# KeyBoard.net
KiCad netlist of a schematic drawn in Altium Designer
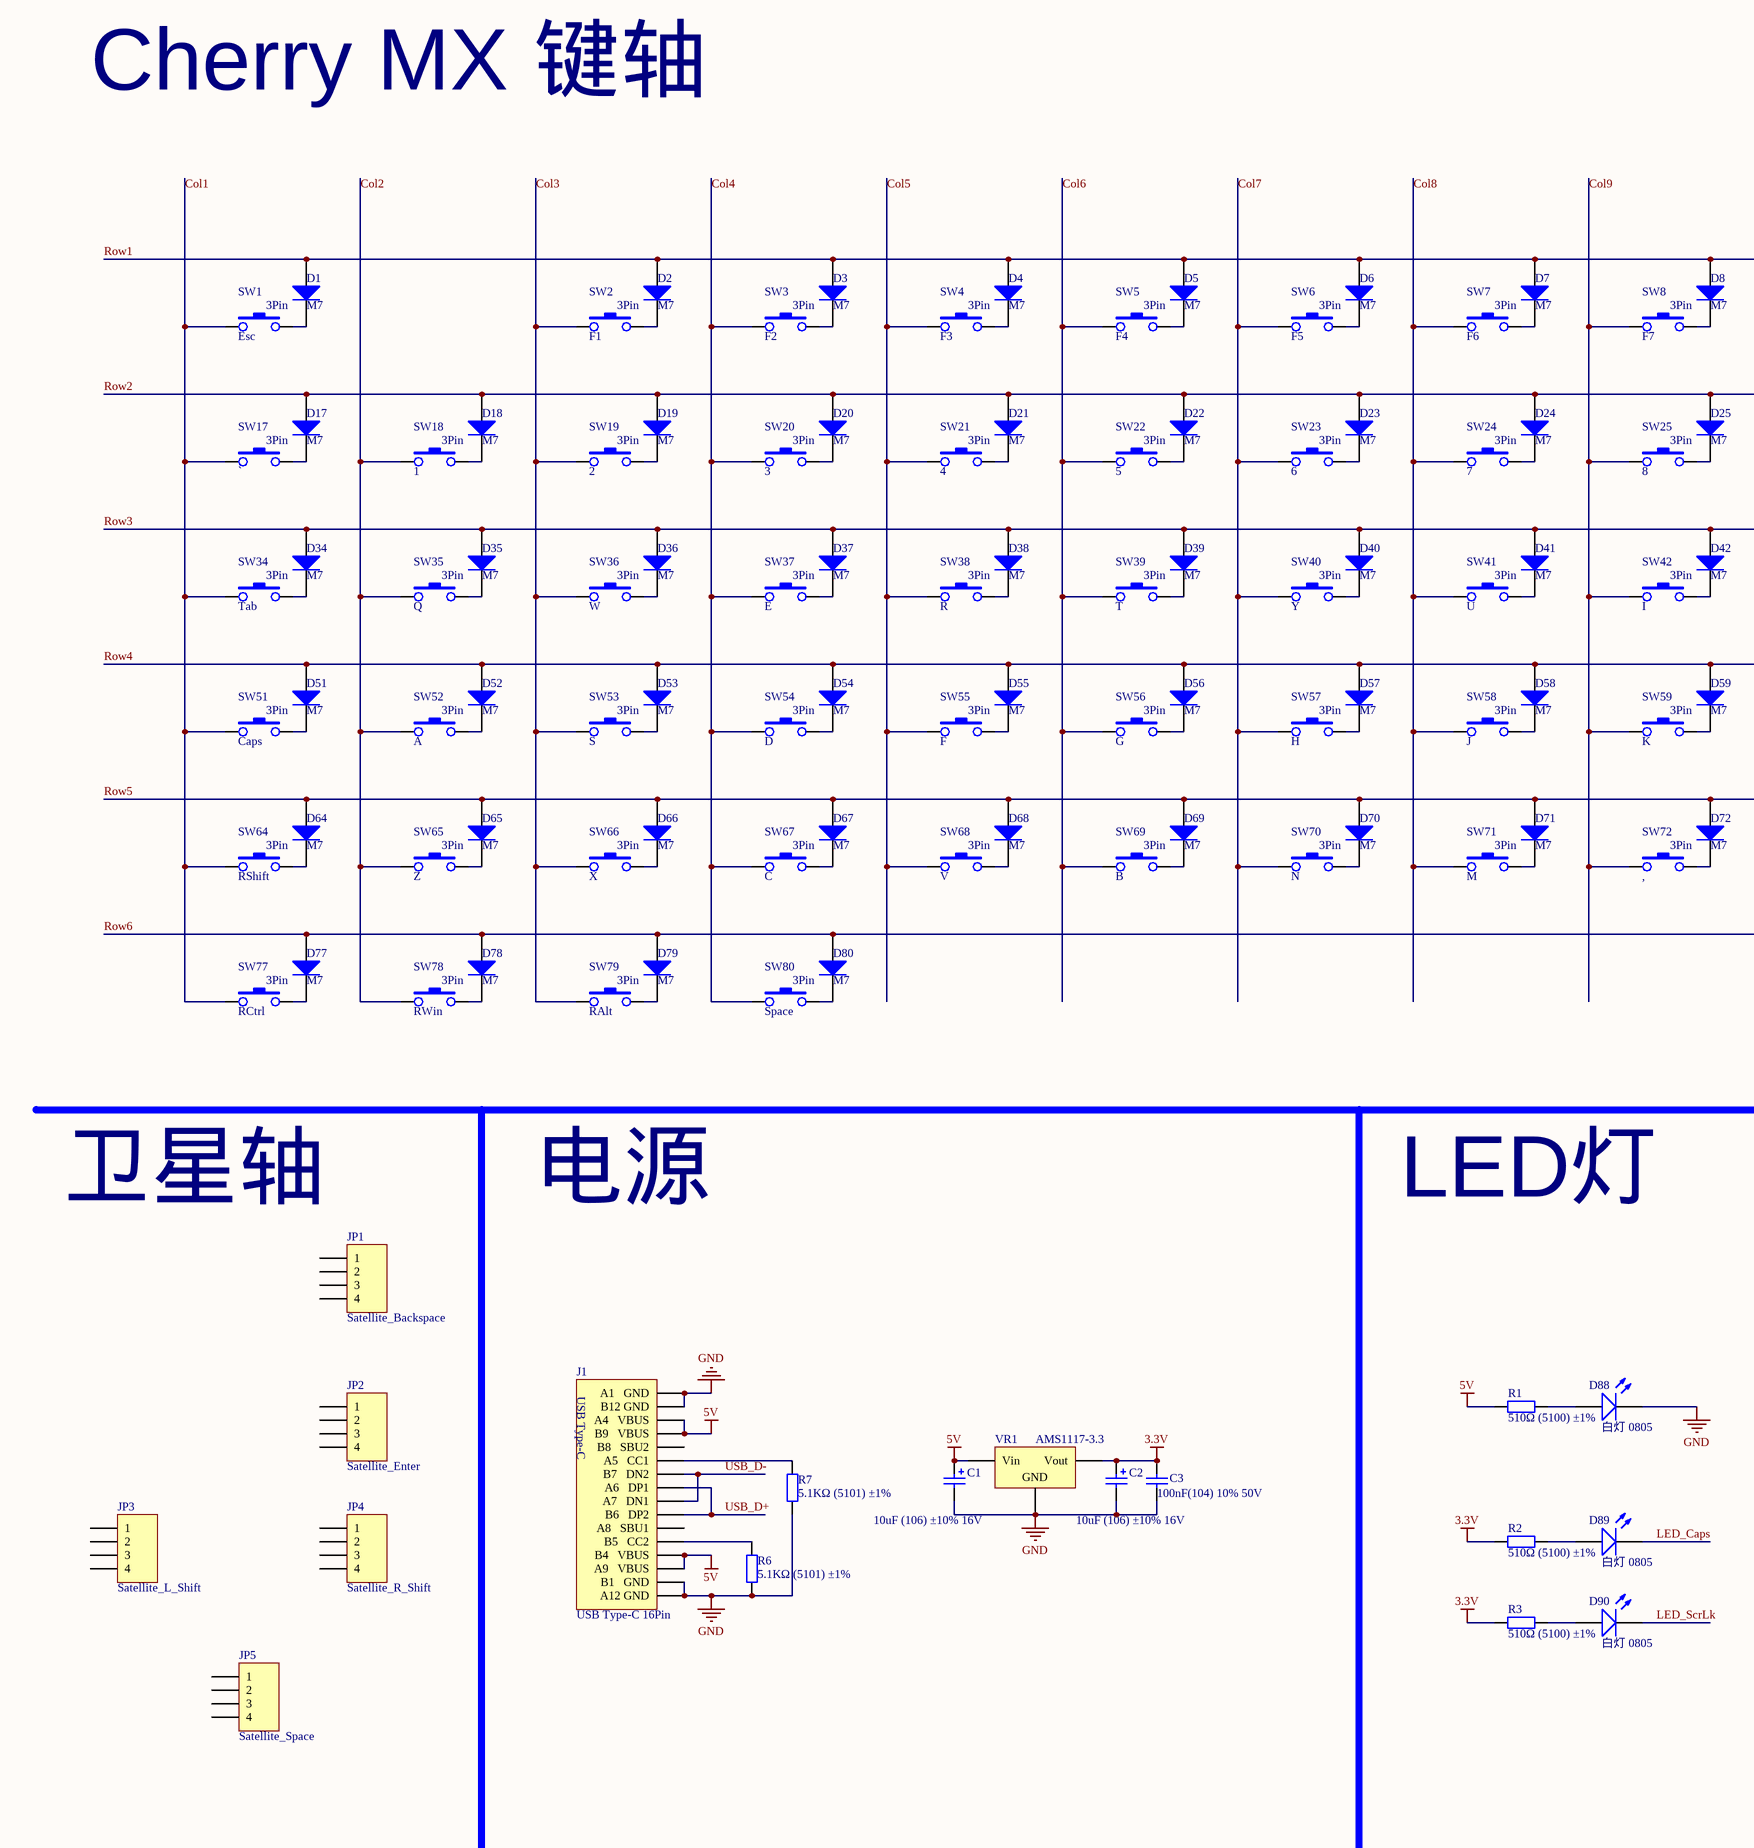
[diagram p0: KeyBoard.SchDoc, left]
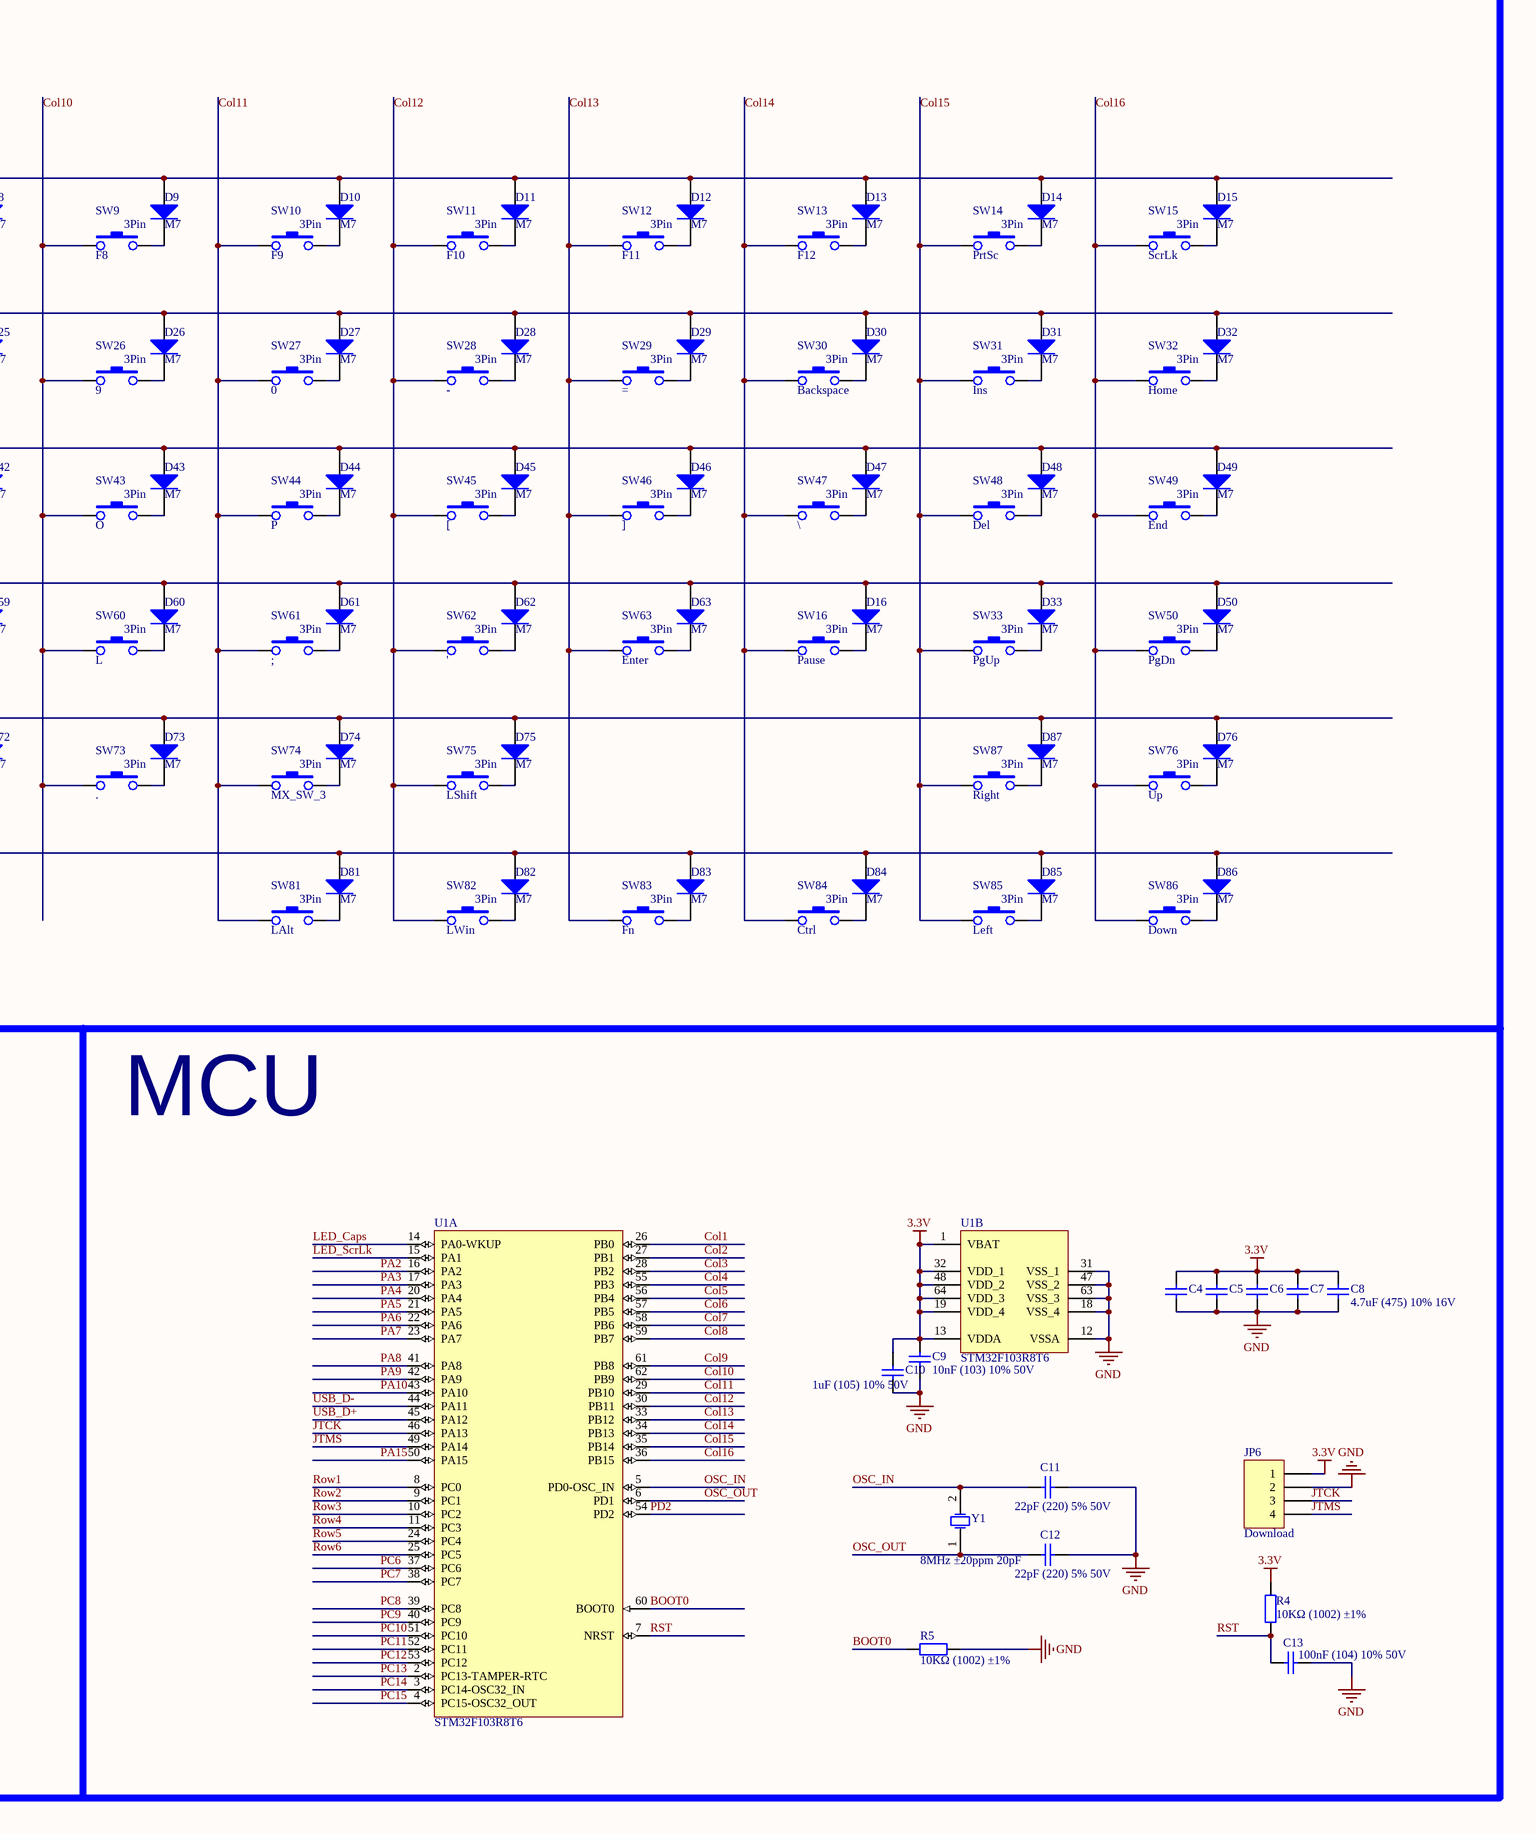
[diagram p1: KeyBoard.SchDoc, right]

(export (version "E")
  (design (tool "Eeschema 10.0.6"))
  (components
    (comp (ref "C1")
      (value "10uF (106) ±10% 16V")
      (footprint "CASE-A_3216")
      (description "钽电容")
      (libsource (lib "Miscellaneous Devices LC") (part "3216 10uF (106) 10% 16V"))
    )
    (comp (ref "C2")
      (value "10uF (106) ±10% 16V")
      (footprint "CASE-A_3216")
      (description "钽电容")
      (libsource (lib "Miscellaneous Devices LC") (part "3216 10uF (106) 10% 16V"))
    )
    (comp (ref "C3")
      (value "100nF(104) 10% 50V")
      (footprint "0805_C")
      (description "贴片电容")
      (libsource (lib "Miscellaneous Devices LC") (part "0805 100nF(104) 10% 50V"))
    )
    (comp (ref "C4")
      (value "100nF (104) 10% 50V")
      (footprint "0603_C")
      (description "贴片电容")
      (libsource (lib "Miscellaneous Devices LC") (part "0603 100nF (104) 10% 50V"))
    )
    (comp (ref "C5")
      (value "100nF (104) 10% 50V")
      (footprint "0603_C")
      (description "贴片电容")
      (libsource (lib "Miscellaneous Devices LC") (part "0603 100nF (104) 10% 50V"))
    )
    (comp (ref "C6")
      (value "100nF (104) 10% 50V")
      (footprint "0603_C")
      (description "贴片电容")
      (libsource (lib "Miscellaneous Devices LC") (part "0603 100nF (104) 10% 50V"))
    )
    (comp (ref "C7")
      (value "100nF (104) 10% 50V")
      (footprint "0603_C")
      (description "贴片电容")
      (libsource (lib "Miscellaneous Devices LC") (part "0603 100nF (104) 10% 50V"))
    )
    (comp (ref "C8")
      (value "4.7uF (475) 10% 16V")
      (footprint "0603_C")
      (description "贴片电容")
      (libsource (lib "Miscellaneous Devices LC") (part "0603 4.7uF (475) 10% 16V"))
    )
    (comp (ref "C9")
      (value "10nF (103) 10% 50V")
      (footprint "0603_C")
      (description "贴片电容")
      (libsource (lib "Miscellaneous Devices LC") (part "0603 10nF (103) 10% 50V"))
    )
    (comp (ref "C10")
      (value "1uF (105) 10% 50V")
      (footprint "0603_C")
      (description "贴片电容")
      (libsource (lib "Miscellaneous Devices LC") (part "0603 1uF (105) 10% 50V"))
    )
    (comp (ref "C11")
      (value "22pF (220) 5% 50V")
      (footprint "0603_C")
      (description "贴片电容")
      (libsource (lib "Miscellaneous Devices LC") (part "0603 22pF (220) 5% 50V"))
    )
    (comp (ref "C12")
      (value "22pF (220) 5% 50V")
      (footprint "0603_C")
      (description "贴片电容")
      (libsource (lib "Miscellaneous Devices LC") (part "0603 22pF (220) 5% 50V"))
    )
    (comp (ref "C13")
      (value "100nF (104) 10% 50V")
      (footprint "0603_C")
      (description "贴片电容")
      (libsource (lib "Miscellaneous Devices LC") (part "0603 100nF (104) 10% 50V"))
    )
    (comp (ref "D1")
      (value "M7")
      (footprint "SMA(DO-214AC)_S1")
      (description "二极管")
      (libsource (lib "Miscellaneous Devices LC") (part "SMA(DO-214AC) M7"))
    )
    (comp (ref "D2")
      (value "M7")
      (footprint "SMA(DO-214AC)_S1")
      (description "二极管")
      (libsource (lib "Miscellaneous Devices LC") (part "SMA(DO-214AC) M7"))
    )
    (comp (ref "D3")
      (value "M7")
      (footprint "SMA(DO-214AC)_S1")
      (description "二极管")
      (libsource (lib "Miscellaneous Devices LC") (part "SMA(DO-214AC) M7"))
    )
    (comp (ref "D4")
      (value "M7")
      (footprint "SMA(DO-214AC)_S1")
      (description "二极管")
      (libsource (lib "Miscellaneous Devices LC") (part "SMA(DO-214AC) M7"))
    )
    (comp (ref "D5")
      (value "M7")
      (footprint "SMA(DO-214AC)_S1")
      (description "二极管")
      (libsource (lib "Miscellaneous Devices LC") (part "SMA(DO-214AC) M7"))
    )
    (comp (ref "D6")
      (value "M7")
      (footprint "SMA(DO-214AC)_S1")
      (description "二极管")
      (libsource (lib "Miscellaneous Devices LC") (part "SMA(DO-214AC) M7"))
    )
    (comp (ref "D7")
      (value "M7")
      (footprint "SMA(DO-214AC)_S1")
      (description "二极管")
      (libsource (lib "Miscellaneous Devices LC") (part "SMA(DO-214AC) M7"))
    )
    (comp (ref "D8")
      (value "M7")
      (footprint "SMA(DO-214AC)_S1")
      (description "二极管")
      (libsource (lib "Miscellaneous Devices LC") (part "SMA(DO-214AC) M7"))
    )
    (comp (ref "D9")
      (value "M7")
      (footprint "SMA(DO-214AC)_S1")
      (description "二极管")
      (libsource (lib "Miscellaneous Devices LC") (part "SMA(DO-214AC) M7"))
    )
    (comp (ref "D10")
      (value "M7")
      (footprint "SMA(DO-214AC)_S1")
      (description "二极管")
      (libsource (lib "Miscellaneous Devices LC") (part "SMA(DO-214AC) M7"))
    )
    (comp (ref "D11")
      (value "M7")
      (footprint "SMA(DO-214AC)_S1")
      (description "二极管")
      (libsource (lib "Miscellaneous Devices LC") (part "SMA(DO-214AC) M7"))
    )
    (comp (ref "D12")
      (value "M7")
      (footprint "SMA(DO-214AC)_S1")
      (description "二极管")
      (libsource (lib "Miscellaneous Devices LC") (part "SMA(DO-214AC) M7"))
    )
    (comp (ref "D13")
      (value "M7")
      (footprint "SMA(DO-214AC)_S1")
      (description "二极管")
      (libsource (lib "Miscellaneous Devices LC") (part "SMA(DO-214AC) M7"))
    )
    (comp (ref "D14")
      (value "M7")
      (footprint "SMA(DO-214AC)_S1")
      (description "二极管")
      (libsource (lib "Miscellaneous Devices LC") (part "SMA(DO-214AC) M7"))
    )
    (comp (ref "D15")
      (value "M7")
      (footprint "SMA(DO-214AC)_S1")
      (description "二极管")
      (libsource (lib "Miscellaneous Devices LC") (part "SMA(DO-214AC) M7"))
    )
    (comp (ref "D16")
      (value "M7")
      (footprint "SMA(DO-214AC)_S1")
      (description "二极管")
      (libsource (lib "Miscellaneous Devices LC") (part "SMA(DO-214AC) M7"))
    )
    (comp (ref "D17")
      (value "M7")
      (footprint "SMA(DO-214AC)_S1")
      (description "二极管")
      (libsource (lib "Miscellaneous Devices LC") (part "SMA(DO-214AC) M7"))
    )
    (comp (ref "D18")
      (value "M7")
      (footprint "SMA(DO-214AC)_S1")
      (description "二极管")
      (libsource (lib "Miscellaneous Devices LC") (part "SMA(DO-214AC) M7"))
    )
    (comp (ref "D19")
      (value "M7")
      (footprint "SMA(DO-214AC)_S1")
      (description "二极管")
      (libsource (lib "Miscellaneous Devices LC") (part "SMA(DO-214AC) M7"))
    )
    (comp (ref "D20")
      (value "M7")
      (footprint "SMA(DO-214AC)_S1")
      (description "二极管")
      (libsource (lib "Miscellaneous Devices LC") (part "SMA(DO-214AC) M7"))
    )
    (comp (ref "D21")
      (value "M7")
      (footprint "SMA(DO-214AC)_S1")
      (description "二极管")
      (libsource (lib "Miscellaneous Devices LC") (part "SMA(DO-214AC) M7"))
    )
    (comp (ref "D22")
      (value "M7")
      (footprint "SMA(DO-214AC)_S1")
      (description "二极管")
      (libsource (lib "Miscellaneous Devices LC") (part "SMA(DO-214AC) M7"))
    )
    (comp (ref "D23")
      (value "M7")
      (footprint "SMA(DO-214AC)_S1")
      (description "二极管")
      (libsource (lib "Miscellaneous Devices LC") (part "SMA(DO-214AC) M7"))
    )
    (comp (ref "D24")
      (value "M7")
      (footprint "SMA(DO-214AC)_S1")
      (description "二极管")
      (libsource (lib "Miscellaneous Devices LC") (part "SMA(DO-214AC) M7"))
    )
    (comp (ref "D25")
      (value "M7")
      (footprint "SMA(DO-214AC)_S1")
      (description "二极管")
      (libsource (lib "Miscellaneous Devices LC") (part "SMA(DO-214AC) M7"))
    )
    (comp (ref "D26")
      (value "M7")
      (footprint "SMA(DO-214AC)_S1")
      (description "二极管")
      (libsource (lib "Miscellaneous Devices LC") (part "SMA(DO-214AC) M7"))
    )
    (comp (ref "D27")
      (value "M7")
      (footprint "SMA(DO-214AC)_S1")
      (description "二极管")
      (libsource (lib "Miscellaneous Devices LC") (part "SMA(DO-214AC) M7"))
    )
    (comp (ref "D28")
      (value "M7")
      (footprint "SMA(DO-214AC)_S1")
      (description "二极管")
      (libsource (lib "Miscellaneous Devices LC") (part "SMA(DO-214AC) M7"))
    )
    (comp (ref "D29")
      (value "M7")
      (footprint "SMA(DO-214AC)_S1")
      (description "二极管")
      (libsource (lib "Miscellaneous Devices LC") (part "SMA(DO-214AC) M7"))
    )
    (comp (ref "D30")
      (value "M7")
      (footprint "SMA(DO-214AC)_S1")
      (description "二极管")
      (libsource (lib "Miscellaneous Devices LC") (part "SMA(DO-214AC) M7"))
    )
    (comp (ref "D31")
      (value "M7")
      (footprint "SMA(DO-214AC)_S1")
      (description "二极管")
      (libsource (lib "Miscellaneous Devices LC") (part "SMA(DO-214AC) M7"))
    )
    (comp (ref "D32")
      (value "M7")
      (footprint "SMA(DO-214AC)_S1")
      (description "二极管")
      (libsource (lib "Miscellaneous Devices LC") (part "SMA(DO-214AC) M7"))
    )
    (comp (ref "D33")
      (value "M7")
      (footprint "SMA(DO-214AC)_S1")
      (description "二极管")
      (libsource (lib "Miscellaneous Devices LC") (part "SMA(DO-214AC) M7"))
    )
    (comp (ref "D34")
      (value "M7")
      (footprint "SMA(DO-214AC)_S1")
      (description "二极管")
      (libsource (lib "Miscellaneous Devices LC") (part "SMA(DO-214AC) M7"))
    )
    (comp (ref "D35")
      (value "M7")
      (footprint "SMA(DO-214AC)_S1")
      (description "二极管")
      (libsource (lib "Miscellaneous Devices LC") (part "SMA(DO-214AC) M7"))
    )
    (comp (ref "D36")
      (value "M7")
      (footprint "SMA(DO-214AC)_S1")
      (description "二极管")
      (libsource (lib "Miscellaneous Devices LC") (part "SMA(DO-214AC) M7"))
    )
    (comp (ref "D37")
      (value "M7")
      (footprint "SMA(DO-214AC)_S1")
      (description "二极管")
      (libsource (lib "Miscellaneous Devices LC") (part "SMA(DO-214AC) M7"))
    )
    (comp (ref "D38")
      (value "M7")
      (footprint "SMA(DO-214AC)_S1")
      (description "二极管")
      (libsource (lib "Miscellaneous Devices LC") (part "SMA(DO-214AC) M7"))
    )
    (comp (ref "D39")
      (value "M7")
      (footprint "SMA(DO-214AC)_S1")
      (description "二极管")
      (libsource (lib "Miscellaneous Devices LC") (part "SMA(DO-214AC) M7"))
    )
    (comp (ref "D40")
      (value "M7")
      (footprint "SMA(DO-214AC)_S1")
      (description "二极管")
      (libsource (lib "Miscellaneous Devices LC") (part "SMA(DO-214AC) M7"))
    )
    (comp (ref "D41")
      (value "M7")
      (footprint "SMA(DO-214AC)_S1")
      (description "二极管")
      (libsource (lib "Miscellaneous Devices LC") (part "SMA(DO-214AC) M7"))
    )
    (comp (ref "D42")
      (value "M7")
      (footprint "SMA(DO-214AC)_S1")
      (description "二极管")
      (libsource (lib "Miscellaneous Devices LC") (part "SMA(DO-214AC) M7"))
    )
    (comp (ref "D43")
      (value "M7")
      (footprint "SMA(DO-214AC)_S1")
      (description "二极管")
      (libsource (lib "Miscellaneous Devices LC") (part "SMA(DO-214AC) M7"))
    )
    (comp (ref "D44")
      (value "M7")
      (footprint "SMA(DO-214AC)_S1")
      (description "二极管")
      (libsource (lib "Miscellaneous Devices LC") (part "SMA(DO-214AC) M7"))
    )
    (comp (ref "D45")
      (value "M7")
      (footprint "SMA(DO-214AC)_S1")
      (description "二极管")
      (libsource (lib "Miscellaneous Devices LC") (part "SMA(DO-214AC) M7"))
    )
    (comp (ref "D46")
      (value "M7")
      (footprint "SMA(DO-214AC)_S1")
      (description "二极管")
      (libsource (lib "Miscellaneous Devices LC") (part "SMA(DO-214AC) M7"))
    )
    (comp (ref "D47")
      (value "M7")
      (footprint "SMA(DO-214AC)_S1")
      (description "二极管")
      (libsource (lib "Miscellaneous Devices LC") (part "SMA(DO-214AC) M7"))
    )
    (comp (ref "D48")
      (value "M7")
      (footprint "SMA(DO-214AC)_S1")
      (description "二极管")
      (libsource (lib "Miscellaneous Devices LC") (part "SMA(DO-214AC) M7"))
    )
    (comp (ref "D49")
      (value "M7")
      (footprint "SMA(DO-214AC)_S1")
      (description "二极管")
      (libsource (lib "Miscellaneous Devices LC") (part "SMA(DO-214AC) M7"))
    )
    (comp (ref "D50")
      (value "M7")
      (footprint "SMA(DO-214AC)_S1")
      (description "二极管")
      (libsource (lib "Miscellaneous Devices LC") (part "SMA(DO-214AC) M7"))
    )
    (comp (ref "D51")
      (value "M7")
      (footprint "SMA(DO-214AC)_S1")
      (description "二极管")
      (libsource (lib "Miscellaneous Devices LC") (part "SMA(DO-214AC) M7"))
    )
    (comp (ref "D52")
      (value "M7")
      (footprint "SMA(DO-214AC)_S1")
      (description "二极管")
      (libsource (lib "Miscellaneous Devices LC") (part "SMA(DO-214AC) M7"))
    )
    (comp (ref "D53")
      (value "M7")
      (footprint "SMA(DO-214AC)_S1")
      (description "二极管")
      (libsource (lib "Miscellaneous Devices LC") (part "SMA(DO-214AC) M7"))
    )
    (comp (ref "D54")
      (value "M7")
      (footprint "SMA(DO-214AC)_S1")
      (description "二极管")
      (libsource (lib "Miscellaneous Devices LC") (part "SMA(DO-214AC) M7"))
    )
    (comp (ref "D55")
      (value "M7")
      (footprint "SMA(DO-214AC)_S1")
      (description "二极管")
      (libsource (lib "Miscellaneous Devices LC") (part "SMA(DO-214AC) M7"))
    )
    (comp (ref "D56")
      (value "M7")
      (footprint "SMA(DO-214AC)_S1")
      (description "二极管")
      (libsource (lib "Miscellaneous Devices LC") (part "SMA(DO-214AC) M7"))
    )
    (comp (ref "D57")
      (value "M7")
      (footprint "SMA(DO-214AC)_S1")
      (description "二极管")
      (libsource (lib "Miscellaneous Devices LC") (part "SMA(DO-214AC) M7"))
    )
    (comp (ref "D58")
      (value "M7")
      (footprint "SMA(DO-214AC)_S1")
      (description "二极管")
      (libsource (lib "Miscellaneous Devices LC") (part "SMA(DO-214AC) M7"))
    )
    (comp (ref "D59")
      (value "M7")
      (footprint "SMA(DO-214AC)_S1")
      (description "二极管")
      (libsource (lib "Miscellaneous Devices LC") (part "SMA(DO-214AC) M7"))
    )
    (comp (ref "D60")
      (value "M7")
      (footprint "SMA(DO-214AC)_S1")
      (description "二极管")
      (libsource (lib "Miscellaneous Devices LC") (part "SMA(DO-214AC) M7"))
    )
    (comp (ref "D61")
      (value "M7")
      (footprint "SMA(DO-214AC)_S1")
      (description "二极管")
      (libsource (lib "Miscellaneous Devices LC") (part "SMA(DO-214AC) M7"))
    )
    (comp (ref "D62")
      (value "M7")
      (footprint "SMA(DO-214AC)_S1")
      (description "二极管")
      (libsource (lib "Miscellaneous Devices LC") (part "SMA(DO-214AC) M7"))
    )
    (comp (ref "D63")
      (value "M7")
      (footprint "SMA(DO-214AC)_S1")
      (description "二极管")
      (libsource (lib "Miscellaneous Devices LC") (part "SMA(DO-214AC) M7"))
    )
    (comp (ref "D64")
      (value "M7")
      (footprint "SMA(DO-214AC)_S1")
      (description "二极管")
      (libsource (lib "Miscellaneous Devices LC") (part "SMA(DO-214AC) M7"))
    )
    (comp (ref "D65")
      (value "M7")
      (footprint "SMA(DO-214AC)_S1")
      (description "二极管")
      (libsource (lib "Miscellaneous Devices LC") (part "SMA(DO-214AC) M7"))
    )
    (comp (ref "D66")
      (value "M7")
      (footprint "SMA(DO-214AC)_S1")
      (description "二极管")
      (libsource (lib "Miscellaneous Devices LC") (part "SMA(DO-214AC) M7"))
    )
    (comp (ref "D67")
      (value "M7")
      (footprint "SMA(DO-214AC)_S1")
      (description "二极管")
      (libsource (lib "Miscellaneous Devices LC") (part "SMA(DO-214AC) M7"))
    )
    (comp (ref "D68")
      (value "M7")
      (footprint "SMA(DO-214AC)_S1")
      (description "二极管")
      (libsource (lib "Miscellaneous Devices LC") (part "SMA(DO-214AC) M7"))
    )
    (comp (ref "D69")
      (value "M7")
      (footprint "SMA(DO-214AC)_S1")
      (description "二极管")
      (libsource (lib "Miscellaneous Devices LC") (part "SMA(DO-214AC) M7"))
    )
    (comp (ref "D70")
      (value "M7")
      (footprint "SMA(DO-214AC)_S1")
      (description "二极管")
      (libsource (lib "Miscellaneous Devices LC") (part "SMA(DO-214AC) M7"))
    )
    (comp (ref "D71")
      (value "M7")
      (footprint "SMA(DO-214AC)_S1")
      (description "二极管")
      (libsource (lib "Miscellaneous Devices LC") (part "SMA(DO-214AC) M7"))
    )
    (comp (ref "D72")
      (value "M7")
      (footprint "SMA(DO-214AC)_S1")
      (description "二极管")
      (libsource (lib "Miscellaneous Devices LC") (part "SMA(DO-214AC) M7"))
    )
    (comp (ref "D73")
      (value "M7")
      (footprint "SMA(DO-214AC)_S1")
      (description "二极管")
      (libsource (lib "Miscellaneous Devices LC") (part "SMA(DO-214AC) M7"))
    )
    (comp (ref "D74")
      (value "M7")
      (footprint "SMA(DO-214AC)_S1")
      (description "二极管")
      (libsource (lib "Miscellaneous Devices LC") (part "SMA(DO-214AC) M7"))
    )
    (comp (ref "D75")
      (value "M7")
      (footprint "SMA(DO-214AC)_S1")
      (description "二极管")
      (libsource (lib "Miscellaneous Devices LC") (part "SMA(DO-214AC) M7"))
    )
    (comp (ref "D76")
      (value "M7")
      (footprint "SMA(DO-214AC)_S1")
      (description "二极管")
      (libsource (lib "Miscellaneous Devices LC") (part "SMA(DO-214AC) M7"))
    )
    (comp (ref "D77")
      (value "M7")
      (footprint "SMA(DO-214AC)_S1")
      (description "二极管")
      (libsource (lib "Miscellaneous Devices LC") (part "SMA(DO-214AC) M7"))
    )
    (comp (ref "D78")
      (value "M7")
      (footprint "SMA(DO-214AC)_S1")
      (description "二极管")
      (libsource (lib "Miscellaneous Devices LC") (part "SMA(DO-214AC) M7"))
    )
    (comp (ref "D79")
      (value "M7")
      (footprint "SMA(DO-214AC)_S1")
      (description "二极管")
      (libsource (lib "Miscellaneous Devices LC") (part "SMA(DO-214AC) M7"))
    )
    (comp (ref "D80")
      (value "M7")
      (footprint "SMA(DO-214AC)_S1")
      (description "二极管")
      (libsource (lib "Miscellaneous Devices LC") (part "SMA(DO-214AC) M7"))
    )
    (comp (ref "D81")
      (value "M7")
      (footprint "SMA(DO-214AC)_S1")
      (description "二极管")
      (libsource (lib "Miscellaneous Devices LC") (part "SMA(DO-214AC) M7"))
    )
    (comp (ref "D82")
      (value "M7")
      (footprint "SMA(DO-214AC)_S1")
      (description "二极管")
      (libsource (lib "Miscellaneous Devices LC") (part "SMA(DO-214AC) M7"))
    )
    (comp (ref "D83")
      (value "M7")
      (footprint "SMA(DO-214AC)_S1")
      (description "二极管")
      (libsource (lib "Miscellaneous Devices LC") (part "SMA(DO-214AC) M7"))
    )
    (comp (ref "D84")
      (value "M7")
      (footprint "SMA(DO-214AC)_S1")
      (description "二极管")
      (libsource (lib "Miscellaneous Devices LC") (part "SMA(DO-214AC) M7"))
    )
    (comp (ref "D85")
      (value "M7")
      (footprint "SMA(DO-214AC)_S1")
      (description "二极管")
      (libsource (lib "Miscellaneous Devices LC") (part "SMA(DO-214AC) M7"))
    )
    (comp (ref "D86")
      (value "M7")
      (footprint "SMA(DO-214AC)_S1")
      (description "二极管")
      (libsource (lib "Miscellaneous Devices LC") (part "SMA(DO-214AC) M7"))
    )
    (comp (ref "D87")
      (value "M7")
      (footprint "SMA(DO-214AC)_S1")
      (description "二极管")
      (libsource (lib "Miscellaneous Devices LC") (part "SMA(DO-214AC) M7"))
    )
    (comp (ref "D88")
      (value "白灯 0805")
      (footprint "0805_LED_S1")
      (description "发光二极管")
      (libsource (lib "Miscellaneous Devices LC") (part "0805 白灯"))
    )
    (comp (ref "D89")
      (value "白灯 0805")
      (footprint "0805_LED_S1")
      (description "发光二极管")
      (libsource (lib "Miscellaneous Devices LC") (part "0805 白灯"))
    )
    (comp (ref "D90")
      (value "白灯 0805")
      (footprint "0805_LED_S1")
      (description "发光二极管")
      (libsource (lib "Miscellaneous Devices LC") (part "0805 白灯"))
    )
    (comp (ref "J1")
      (value "USB Type-C 16Pin")
      (footprint "USB Type-C 16Pin")
      (libsource (lib "KeyBoard") (part "USB Type-C 16Pin"))
    )
    (comp (ref "JP1")
      (value "Satellite_Backspace")
      (footprint "1x2")
      (description "Header, 4-Pin")
      (fields (field (name "PUBLISHER") "Altium Limited"))
      (libsource (lib "Miscellaneous Connectors") (part "Header 4"))
    )
    (comp (ref "JP2")
      (value "Satellite_Enter")
      (footprint "1x2")
      (description "Header, 4-Pin")
      (fields (field (name "PUBLISHER") "Altium Limited"))
      (libsource (lib "Miscellaneous Connectors") (part "Header 4"))
    )
    (comp (ref "JP3")
      (value "Satellite_L_Shift")
      (footprint "1x2")
      (description "Header, 4-Pin")
      (fields (field (name "PUBLISHER") "Altium Limited"))
      (libsource (lib "Miscellaneous Connectors") (part "Header 4"))
    )
    (comp (ref "JP4")
      (value "Satellite_R_Shift")
      (footprint "1x2")
      (description "Header, 4-Pin")
      (fields (field (name "PUBLISHER") "Altium Limited"))
      (libsource (lib "Miscellaneous Connectors") (part "Header 4"))
    )
    (comp (ref "JP5")
      (value "Satellite_Space")
      (footprint "1x6.25")
      (description "Header, 4-Pin")
      (fields (field (name "PUBLISHER") "Altium Limited"))
      (libsource (lib "Miscellaneous Connectors") (part "Header 4"))
    )
    (comp (ref "JP6")
      (value "Download")
      (footprint "HDR1X4")
      (description "Header, 4-Pin")
      (fields (field (name "PUBLISHER") "Altium Limited"))
      (libsource (lib "") (part "Header 4_1"))
    )
    (comp (ref "R1")
      (value "510Ω (5100) ±1%")
      (footprint "0805_R")
      (description "贴片电阻")
      (libsource (lib "Miscellaneous Devices LC") (part "0805 510Ω (5100) 1%"))
    )
    (comp (ref "R2")
      (value "510Ω (5100) ±1%")
      (footprint "0805_R")
      (description "贴片电阻")
      (libsource (lib "Miscellaneous Devices LC") (part "0805 510Ω (5100) 1%"))
    )
    (comp (ref "R3")
      (value "510Ω (5100) ±1%")
      (footprint "0805_R")
      (description "贴片电阻")
      (libsource (lib "Miscellaneous Devices LC") (part "0805 510Ω (5100) 1%"))
    )
    (comp (ref "R4")
      (value "10KΩ (1002) ±1%")
      (footprint "0603_R")
      (description "贴片电阻")
      (libsource (lib "Miscellaneous Devices LC") (part "0603 10KΩ (1002) 1%"))
    )
    (comp (ref "R5")
      (value "10KΩ (1002) ±1%")
      (footprint "0603_R")
      (description "贴片电阻")
      (libsource (lib "") (part "0603 10KΩ (1002) 1%_1"))
    )
    (comp (ref "R6")
      (value "5.1KΩ (5101) ±1%")
      (footprint "0805_R")
      (description "贴片电阻")
      (libsource (lib "Miscellaneous Devices LC") (part "0805 5.1KΩ (5101) 1%"))
    )
    (comp (ref "R7")
      (value "5.1KΩ (5101) ±1%")
      (footprint "0805_R")
      (description "贴片电阻")
      (libsource (lib "Miscellaneous Devices LC") (part "0805 5.1KΩ (5101) 1%"))
    )
    (comp (ref "SW1")
      (value "Esc")
      (footprint "MX_SW_3")
      (description "without Fixation pins  1-Pole")
      (libsource (lib "KeyBoard") (part "MX_SW_3"))
    )
    (comp (ref "SW2")
      (value "F1")
      (footprint "MX_SW_3")
      (description "without Fixation pins  1-Pole")
      (libsource (lib "KeyBoard") (part "MX_SW_3"))
    )
    (comp (ref "SW3")
      (value "F2")
      (footprint "MX_SW_3")
      (description "without Fixation pins  1-Pole")
      (libsource (lib "KeyBoard") (part "MX_SW_3"))
    )
    (comp (ref "SW4")
      (value "F3")
      (footprint "MX_SW_3")
      (description "without Fixation pins  1-Pole")
      (libsource (lib "KeyBoard") (part "MX_SW_3"))
    )
    (comp (ref "SW5")
      (value "F4")
      (footprint "MX_SW_3")
      (description "without Fixation pins  1-Pole")
      (libsource (lib "KeyBoard") (part "MX_SW_3"))
    )
    (comp (ref "SW6")
      (value "F5")
      (footprint "MX_SW_3")
      (description "without Fixation pins  1-Pole")
      (libsource (lib "KeyBoard") (part "MX_SW_3"))
    )
    (comp (ref "SW7")
      (value "F6")
      (footprint "MX_SW_3")
      (description "without Fixation pins  1-Pole")
      (libsource (lib "KeyBoard") (part "MX_SW_3"))
    )
    (comp (ref "SW8")
      (value "F7")
      (footprint "MX_SW_3")
      (description "without Fixation pins  1-Pole")
      (libsource (lib "KeyBoard") (part "MX_SW_3"))
    )
    (comp (ref "SW9")
      (value "F8")
      (footprint "MX_SW_3")
      (description "without Fixation pins  1-Pole")
      (libsource (lib "KeyBoard") (part "MX_SW_3"))
    )
    (comp (ref "SW10")
      (value "F9")
      (footprint "MX_SW_3")
      (description "without Fixation pins  1-Pole")
      (libsource (lib "KeyBoard") (part "MX_SW_3"))
    )
    (comp (ref "SW11")
      (value "F10")
      (footprint "MX_SW_3")
      (description "without Fixation pins  1-Pole")
      (libsource (lib "KeyBoard") (part "MX_SW_3"))
    )
    (comp (ref "SW12")
      (value "F11")
      (footprint "MX_SW_3")
      (description "without Fixation pins  1-Pole")
      (libsource (lib "KeyBoard") (part "MX_SW_3"))
    )
    (comp (ref "SW13")
      (value "F12")
      (footprint "MX_SW_3")
      (description "without Fixation pins  1-Pole")
      (libsource (lib "KeyBoard") (part "MX_SW_3"))
    )
    (comp (ref "SW14")
      (value "PrtSc")
      (footprint "MX_SW_3")
      (description "without Fixation pins  1-Pole")
      (libsource (lib "KeyBoard") (part "MX_SW_3"))
    )
    (comp (ref "SW15")
      (value "ScrLk")
      (footprint "MX_SW_3")
      (description "without Fixation pins  1-Pole")
      (libsource (lib "KeyBoard") (part "MX_SW_3"))
    )
    (comp (ref "SW16")
      (value "Pause")
      (footprint "MX_SW_3")
      (description "without Fixation pins  1-Pole")
      (libsource (lib "KeyBoard") (part "MX_SW_3"))
    )
    (comp (ref "SW17")
      (value "`")
      (footprint "MX_SW_3")
      (description "without Fixation pins  1-Pole")
      (libsource (lib "KeyBoard") (part "MX_SW_3"))
    )
    (comp (ref "SW18")
      (value "1")
      (footprint "MX_SW_3")
      (description "without Fixation pins  1-Pole")
      (libsource (lib "KeyBoard") (part "MX_SW_3"))
    )
    (comp (ref "SW19")
      (value "2")
      (footprint "MX_SW_3")
      (description "without Fixation pins  1-Pole")
      (libsource (lib "KeyBoard") (part "MX_SW_3"))
    )
    (comp (ref "SW20")
      (value "3")
      (footprint "MX_SW_3")
      (description "without Fixation pins  1-Pole")
      (libsource (lib "KeyBoard") (part "MX_SW_3"))
    )
    (comp (ref "SW21")
      (value "4")
      (footprint "MX_SW_3")
      (description "without Fixation pins  1-Pole")
      (libsource (lib "KeyBoard") (part "MX_SW_3"))
    )
    (comp (ref "SW22")
      (value "5")
      (footprint "MX_SW_3")
      (description "without Fixation pins  1-Pole")
      (libsource (lib "KeyBoard") (part "MX_SW_3"))
    )
    (comp (ref "SW23")
      (value "6")
      (footprint "MX_SW_3")
      (description "without Fixation pins  1-Pole")
      (libsource (lib "KeyBoard") (part "MX_SW_3"))
    )
    (comp (ref "SW24")
      (value "7")
      (footprint "MX_SW_3")
      (description "without Fixation pins  1-Pole")
      (libsource (lib "KeyBoard") (part "MX_SW_3"))
    )
    (comp (ref "SW25")
      (value "8")
      (footprint "MX_SW_3")
      (description "without Fixation pins  1-Pole")
      (libsource (lib "KeyBoard") (part "MX_SW_3"))
    )
    (comp (ref "SW26")
      (value "9")
      (footprint "MX_SW_3")
      (description "without Fixation pins  1-Pole")
      (libsource (lib "KeyBoard") (part "MX_SW_3"))
    )
    (comp (ref "SW27")
      (value "0")
      (footprint "MX_SW_3")
      (description "without Fixation pins  1-Pole")
      (libsource (lib "KeyBoard") (part "MX_SW_3"))
    )
    (comp (ref "SW28")
      (value "-")
      (footprint "MX_SW_3")
      (description "without Fixation pins  1-Pole")
      (libsource (lib "KeyBoard") (part "MX_SW_3"))
    )
    (comp (ref "SW29")
      (value "~")
      (footprint "MX_SW_3")
      (description "without Fixation pins  1-Pole")
      (libsource (lib "KeyBoard") (part "MX_SW_3"))
    )
    (comp (ref "SW30")
      (value "Backspace")
      (footprint "MX_SW_3")
      (description "without Fixation pins  1-Pole")
      (libsource (lib "KeyBoard") (part "MX_SW_3"))
    )
    (comp (ref "SW31")
      (value "Ins")
      (footprint "MX_SW_3")
      (description "without Fixation pins  1-Pole")
      (libsource (lib "KeyBoard") (part "MX_SW_3"))
    )
    (comp (ref "SW32")
      (value "Home")
      (footprint "MX_SW_3")
      (description "without Fixation pins  1-Pole")
      (libsource (lib "KeyBoard") (part "MX_SW_3"))
    )
    (comp (ref "SW33")
      (value "PgUp")
      (footprint "MX_SW_3")
      (description "without Fixation pins  1-Pole")
      (libsource (lib "KeyBoard") (part "MX_SW_3"))
    )
    (comp (ref "SW34")
      (value "Tab")
      (footprint "MX_SW_3")
      (description "without Fixation pins  1-Pole")
      (libsource (lib "KeyBoard") (part "MX_SW_3"))
    )
    (comp (ref "SW35")
      (value "Q")
      (footprint "MX_SW_3")
      (description "without Fixation pins  1-Pole")
      (libsource (lib "KeyBoard") (part "MX_SW_3"))
    )
    (comp (ref "SW36")
      (value "W")
      (footprint "MX_SW_3")
      (description "without Fixation pins  1-Pole")
      (libsource (lib "KeyBoard") (part "MX_SW_3"))
    )
    (comp (ref "SW37")
      (value "E")
      (footprint "MX_SW_3")
      (description "without Fixation pins  1-Pole")
      (libsource (lib "KeyBoard") (part "MX_SW_3"))
    )
    (comp (ref "SW38")
      (value "R")
      (footprint "MX_SW_3")
      (description "without Fixation pins  1-Pole")
      (libsource (lib "KeyBoard") (part "MX_SW_3"))
    )
    (comp (ref "SW39")
      (value "T")
      (footprint "MX_SW_3")
      (description "without Fixation pins  1-Pole")
      (libsource (lib "KeyBoard") (part "MX_SW_3"))
    )
    (comp (ref "SW40")
      (value "Y")
      (footprint "MX_SW_3")
      (description "without Fixation pins  1-Pole")
      (libsource (lib "KeyBoard") (part "MX_SW_3"))
    )
    (comp (ref "SW41")
      (value "U")
      (footprint "MX_SW_3")
      (description "without Fixation pins  1-Pole")
      (libsource (lib "KeyBoard") (part "MX_SW_3"))
    )
    (comp (ref "SW42")
      (value "I")
      (footprint "MX_SW_3")
      (description "without Fixation pins  1-Pole")
      (libsource (lib "KeyBoard") (part "MX_SW_3"))
    )
    (comp (ref "SW43")
      (value "O")
      (footprint "MX_SW_3")
      (description "without Fixation pins  1-Pole")
      (libsource (lib "KeyBoard") (part "MX_SW_3"))
    )
    (comp (ref "SW44")
      (value "P")
      (footprint "MX_SW_3")
      (description "without Fixation pins  1-Pole")
      (libsource (lib "KeyBoard") (part "MX_SW_3"))
    )
    (comp (ref "SW45")
      (value "[")
      (footprint "MX_SW_3")
      (description "without Fixation pins  1-Pole")
      (libsource (lib "KeyBoard") (part "MX_SW_3"))
    )
    (comp (ref "SW46")
      (value "]")
      (footprint "MX_SW_3")
      (description "without Fixation pins  1-Pole")
      (libsource (lib "KeyBoard") (part "MX_SW_3"))
    )
    (comp (ref "SW47")
      (value "\\")
      (footprint "MX_SW_3")
      (description "without Fixation pins  1-Pole")
      (libsource (lib "KeyBoard") (part "MX_SW_3"))
    )
    (comp (ref "SW48")
      (value "Del")
      (footprint "MX_SW_3")
      (description "without Fixation pins  1-Pole")
      (libsource (lib "KeyBoard") (part "MX_SW_3"))
    )
    (comp (ref "SW49")
      (value "End")
      (footprint "MX_SW_3")
      (description "without Fixation pins  1-Pole")
      (libsource (lib "KeyBoard") (part "MX_SW_3"))
    )
    (comp (ref "SW50")
      (value "PgDn")
      (footprint "MX_SW_3")
      (description "without Fixation pins  1-Pole")
      (libsource (lib "KeyBoard") (part "MX_SW_3"))
    )
    (comp (ref "SW51")
      (value "Caps")
      (footprint "MX_SW_3")
      (description "without Fixation pins  1-Pole")
      (libsource (lib "KeyBoard") (part "MX_SW_3"))
    )
    (comp (ref "SW52")
      (value "A")
      (footprint "MX_SW_3")
      (description "without Fixation pins  1-Pole")
      (libsource (lib "KeyBoard") (part "MX_SW_3"))
    )
    (comp (ref "SW53")
      (value "S")
      (footprint "MX_SW_3")
      (description "without Fixation pins  1-Pole")
      (libsource (lib "KeyBoard") (part "MX_SW_3"))
    )
    (comp (ref "SW54")
      (value "D")
      (footprint "MX_SW_3")
      (description "without Fixation pins  1-Pole")
      (libsource (lib "KeyBoard") (part "MX_SW_3"))
    )
    (comp (ref "SW55")
      (value "F")
      (footprint "MX_SW_3")
      (description "without Fixation pins  1-Pole")
      (libsource (lib "KeyBoard") (part "MX_SW_3"))
    )
    (comp (ref "SW56")
      (value "G")
      (footprint "MX_SW_3")
      (description "without Fixation pins  1-Pole")
      (libsource (lib "KeyBoard") (part "MX_SW_3"))
    )
    (comp (ref "SW57")
      (value "H")
      (footprint "MX_SW_3")
      (description "without Fixation pins  1-Pole")
      (libsource (lib "KeyBoard") (part "MX_SW_3"))
    )
    (comp (ref "SW58")
      (value "J")
      (footprint "MX_SW_3")
      (description "without Fixation pins  1-Pole")
      (libsource (lib "KeyBoard") (part "MX_SW_3"))
    )
    (comp (ref "SW59")
      (value "K")
      (footprint "MX_SW_3")
      (description "without Fixation pins  1-Pole")
      (libsource (lib "KeyBoard") (part "MX_SW_3"))
    )
    (comp (ref "SW60")
      (value "L")
      (footprint "MX_SW_3")
      (description "without Fixation pins  1-Pole")
      (libsource (lib "KeyBoard") (part "MX_SW_3"))
    )
    (comp (ref "SW61")
      (value ";")
      (footprint "MX_SW_3")
      (description "without Fixation pins  1-Pole")
      (libsource (lib "KeyBoard") (part "MX_SW_3"))
    )
    (comp (ref "SW62")
      (value "'")
      (footprint "MX_SW_3")
      (description "without Fixation pins  1-Pole")
      (libsource (lib "KeyBoard") (part "MX_SW_3"))
    )
    (comp (ref "SW63")
      (value "Enter")
      (footprint "MX_SW_3")
      (description "without Fixation pins  1-Pole")
      (libsource (lib "KeyBoard") (part "MX_SW_3"))
    )
    (comp (ref "SW64")
      (value "RShift")
      (footprint "MX_SW_3")
      (description "without Fixation pins  1-Pole")
      (libsource (lib "KeyBoard") (part "MX_SW_3"))
    )
    (comp (ref "SW65")
      (value "Z")
      (footprint "MX_SW_3")
      (description "without Fixation pins  1-Pole")
      (libsource (lib "KeyBoard") (part "MX_SW_3"))
    )
    (comp (ref "SW66")
      (value "X")
      (footprint "MX_SW_3")
      (description "without Fixation pins  1-Pole")
      (libsource (lib "KeyBoard") (part "MX_SW_3"))
    )
    (comp (ref "SW67")
      (value "C")
      (footprint "MX_SW_3")
      (description "without Fixation pins  1-Pole")
      (libsource (lib "KeyBoard") (part "MX_SW_3"))
    )
    (comp (ref "SW68")
      (value "V")
      (footprint "MX_SW_3")
      (description "without Fixation pins  1-Pole")
      (libsource (lib "KeyBoard") (part "MX_SW_3"))
    )
    (comp (ref "SW69")
      (value "B")
      (footprint "MX_SW_3")
      (description "without Fixation pins  1-Pole")
      (libsource (lib "KeyBoard") (part "MX_SW_3"))
    )
    (comp (ref "SW70")
      (value "N")
      (footprint "MX_SW_3")
      (description "without Fixation pins  1-Pole")
      (libsource (lib "KeyBoard") (part "MX_SW_3"))
    )
    (comp (ref "SW71")
      (value "M")
      (footprint "MX_SW_3")
      (description "without Fixation pins  1-Pole")
      (libsource (lib "KeyBoard") (part "MX_SW_3"))
    )
    (comp (ref "SW72")
      (value ",")
      (footprint "MX_SW_3")
      (description "without Fixation pins  1-Pole")
      (libsource (lib "KeyBoard") (part "MX_SW_3"))
    )
    (comp (ref "SW73")
      (value ".")
      (footprint "MX_SW_3")
      (description "without Fixation pins  1-Pole")
      (libsource (lib "KeyBoard") (part "MX_SW_3"))
    )
    (comp (ref "SW74")
      (value "MX_SW_3")
      (footprint "MX_SW_3")
      (description "without Fixation pins  1-Pole")
      (libsource (lib "KeyBoard") (part "MX_SW_3"))
    )
    (comp (ref "SW75")
      (value "LShift")
      (footprint "MX_SW_3")
      (description "without Fixation pins  1-Pole")
      (libsource (lib "KeyBoard") (part "MX_SW_3"))
    )
    (comp (ref "SW76")
      (value "Up")
      (footprint "MX_SW_3")
      (description "without Fixation pins  1-Pole")
      (libsource (lib "KeyBoard") (part "MX_SW_3"))
    )
    (comp (ref "SW77")
      (value "RCtrl")
      (footprint "MX_SW_3")
      (description "without Fixation pins  1-Pole")
      (libsource (lib "KeyBoard") (part "MX_SW_3"))
    )
    (comp (ref "SW78")
      (value "RWin")
      (footprint "MX_SW_3")
      (description "without Fixation pins  1-Pole")
      (libsource (lib "KeyBoard") (part "MX_SW_3"))
    )
    (comp (ref "SW79")
      (value "RAlt")
      (footprint "MX_SW_3")
      (description "without Fixation pins  1-Pole")
      (libsource (lib "KeyBoard") (part "MX_SW_3"))
    )
    (comp (ref "SW80")
      (value "Space")
      (footprint "MX_SW_3")
      (description "without Fixation pins  1-Pole")
      (libsource (lib "KeyBoard") (part "MX_SW_3"))
    )
    (comp (ref "SW81")
      (value "LAlt")
      (footprint "MX_SW_3")
      (description "without Fixation pins  1-Pole")
      (libsource (lib "KeyBoard") (part "MX_SW_3"))
    )
    (comp (ref "SW82")
      (value "LWin")
      (footprint "MX_SW_3")
      (description "without Fixation pins  1-Pole")
      (libsource (lib "KeyBoard") (part "MX_SW_3"))
    )
    (comp (ref "SW83")
      (value "Fn")
      (footprint "MX_SW_3")
      (description "without Fixation pins  1-Pole")
      (libsource (lib "KeyBoard") (part "MX_SW_3"))
    )
    (comp (ref "SW84")
      (value "Ctrl")
      (footprint "MX_SW_3")
      (description "without Fixation pins  1-Pole")
      (libsource (lib "KeyBoard") (part "MX_SW_3"))
    )
    (comp (ref "SW85")
      (value "Left")
      (footprint "MX_SW_3")
      (description "without Fixation pins  1-Pole")
      (libsource (lib "KeyBoard") (part "MX_SW_3"))
    )
    (comp (ref "SW86")
      (value "Down")
      (footprint "MX_SW_3")
      (description "without Fixation pins  1-Pole")
      (libsource (lib "KeyBoard") (part "MX_SW_3"))
    )
    (comp (ref "SW87")
      (value "Right")
      (footprint "MX_SW_3")
      (description "without Fixation pins  1-Pole")
      (libsource (lib "KeyBoard") (part "MX_SW_3"))
    )
    (comp (ref "U1")
      (value "STM32F103R8T6")
      (footprint "LQFP-64_10x10x05P")
      (description "ARM")
      (libsource (lib "Miscellaneous Devices LC") (part "STM32F103R8T6"))
    )
    (comp (ref "VR1")
      (value "AMS1117-3.3")
      (footprint "SOT-223")
      (description "低压差线性稳压(LDO)")
      (libsource (lib "Miscellaneous Devices LC") (part "SOT-223 AMS1117-3.3"))
    )
    (comp (ref "Y1")
      (value "8MHz ±20ppm 20pF")
      (footprint "SMD-5032_2P")
      (description "贴片晶振")
      (libsource (lib "Miscellaneous Devices LC") (part "SMD-5032_2P 8MHz 20ppm 20pF"))
    )
  )
  (nets
    (net (code "1") (name "/BOOT0") (class "Default")
      (node (ref "R5") (pin "1") (pinfunction "1_1") (pintype "passive"))
      (node (ref "U1") (pin "60") (pinfunction "BOOT0_60") (pintype "input"))
    )
    (net (code "2") (name "/Col1") (class "Default")
      (node (ref "SW1") (pin "1") (pinfunction "1_1") (pintype "passive"))
      (node (ref "SW17") (pin "1") (pinfunction "1_1") (pintype "passive"))
      (node (ref "SW34") (pin "1") (pinfunction "1_1") (pintype "passive"))
      (node (ref "SW51") (pin "1") (pinfunction "1_1") (pintype "passive"))
      (node (ref "SW64") (pin "1") (pinfunction "1_1") (pintype "passive"))
      (node (ref "SW77") (pin "1") (pinfunction "1_1") (pintype "passive"))
      (node (ref "U1") (pin "26") (pinfunction "PB0_26") (pintype "bidirectional"))
    )
    (net (code "3") (name "/Col2") (class "Default")
      (node (ref "SW18") (pin "1") (pinfunction "1_1") (pintype "passive"))
      (node (ref "SW35") (pin "1") (pinfunction "1_1") (pintype "passive"))
      (node (ref "SW52") (pin "1") (pinfunction "1_1") (pintype "passive"))
      (node (ref "SW65") (pin "1") (pinfunction "1_1") (pintype "passive"))
      (node (ref "SW78") (pin "1") (pinfunction "1_1") (pintype "passive"))
      (node (ref "U1") (pin "27") (pinfunction "PB1_27") (pintype "bidirectional"))
    )
    (net (code "4") (name "/Col3") (class "Default")
      (node (ref "SW19") (pin "1") (pinfunction "1_1") (pintype "passive"))
      (node (ref "SW2") (pin "1") (pinfunction "1_1") (pintype "passive"))
      (node (ref "SW36") (pin "1") (pinfunction "1_1") (pintype "passive"))
      (node (ref "SW53") (pin "1") (pinfunction "1_1") (pintype "passive"))
      (node (ref "SW66") (pin "1") (pinfunction "1_1") (pintype "passive"))
      (node (ref "SW79") (pin "1") (pinfunction "1_1") (pintype "passive"))
      (node (ref "U1") (pin "28") (pinfunction "PB2_28") (pintype "bidirectional"))
    )
    (net (code "5") (name "/Col4") (class "Default")
      (node (ref "SW20") (pin "1") (pinfunction "1_1") (pintype "passive"))
      (node (ref "SW3") (pin "1") (pinfunction "1_1") (pintype "passive"))
      (node (ref "SW37") (pin "1") (pinfunction "1_1") (pintype "passive"))
      (node (ref "SW54") (pin "1") (pinfunction "1_1") (pintype "passive"))
      (node (ref "SW67") (pin "1") (pinfunction "1_1") (pintype "passive"))
      (node (ref "SW80") (pin "1") (pinfunction "1_1") (pintype "passive"))
      (node (ref "U1") (pin "55") (pinfunction "PB3_55") (pintype "bidirectional"))
    )
    (net (code "6") (name "/Col5") (class "Default")
      (node (ref "SW21") (pin "1") (pinfunction "1_1") (pintype "passive"))
      (node (ref "SW38") (pin "1") (pinfunction "1_1") (pintype "passive"))
      (node (ref "SW4") (pin "1") (pinfunction "1_1") (pintype "passive"))
      (node (ref "SW55") (pin "1") (pinfunction "1_1") (pintype "passive"))
      (node (ref "SW68") (pin "1") (pinfunction "1_1") (pintype "passive"))
      (node (ref "U1") (pin "56") (pinfunction "PB4_56") (pintype "bidirectional"))
    )
    (net (code "7") (name "/Col6") (class "Default")
      (node (ref "SW22") (pin "1") (pinfunction "1_1") (pintype "passive"))
      (node (ref "SW39") (pin "1") (pinfunction "1_1") (pintype "passive"))
      (node (ref "SW5") (pin "1") (pinfunction "1_1") (pintype "passive"))
      (node (ref "SW56") (pin "1") (pinfunction "1_1") (pintype "passive"))
      (node (ref "SW69") (pin "1") (pinfunction "1_1") (pintype "passive"))
      (node (ref "U1") (pin "57") (pinfunction "PB5_57") (pintype "bidirectional"))
    )
    (net (code "8") (name "/Col7") (class "Default")
      (node (ref "SW23") (pin "1") (pinfunction "1_1") (pintype "passive"))
      (node (ref "SW40") (pin "1") (pinfunction "1_1") (pintype "passive"))
      (node (ref "SW57") (pin "1") (pinfunction "1_1") (pintype "passive"))
      (node (ref "SW6") (pin "1") (pinfunction "1_1") (pintype "passive"))
      (node (ref "SW70") (pin "1") (pinfunction "1_1") (pintype "passive"))
      (node (ref "U1") (pin "58") (pinfunction "PB6_58") (pintype "bidirectional"))
    )
    (net (code "9") (name "/Col8") (class "Default")
      (node (ref "SW24") (pin "1") (pinfunction "1_1") (pintype "passive"))
      (node (ref "SW41") (pin "1") (pinfunction "1_1") (pintype "passive"))
      (node (ref "SW58") (pin "1") (pinfunction "1_1") (pintype "passive"))
      (node (ref "SW7") (pin "1") (pinfunction "1_1") (pintype "passive"))
      (node (ref "SW71") (pin "1") (pinfunction "1_1") (pintype "passive"))
      (node (ref "U1") (pin "59") (pinfunction "PB7_59") (pintype "bidirectional"))
    )
    (net (code "10") (name "/Col9") (class "Default")
      (node (ref "SW25") (pin "1") (pinfunction "1_1") (pintype "passive"))
      (node (ref "SW42") (pin "1") (pinfunction "1_1") (pintype "passive"))
      (node (ref "SW59") (pin "1") (pinfunction "1_1") (pintype "passive"))
      (node (ref "SW72") (pin "1") (pinfunction "1_1") (pintype "passive"))
      (node (ref "SW8") (pin "1") (pinfunction "1_1") (pintype "passive"))
      (node (ref "U1") (pin "61") (pinfunction "PB8_61") (pintype "bidirectional"))
    )
    (net (code "11") (name "/Col10") (class "Default")
      (node (ref "SW26") (pin "1") (pinfunction "1_1") (pintype "passive"))
      (node (ref "SW43") (pin "1") (pinfunction "1_1") (pintype "passive"))
      (node (ref "SW60") (pin "1") (pinfunction "1_1") (pintype "passive"))
      (node (ref "SW73") (pin "1") (pinfunction "1_1") (pintype "passive"))
      (node (ref "SW9") (pin "1") (pinfunction "1_1") (pintype "passive"))
      (node (ref "U1") (pin "62") (pinfunction "PB9_62") (pintype "bidirectional"))
    )
    (net (code "12") (name "/Col11") (class "Default")
      (node (ref "SW10") (pin "1") (pinfunction "1_1") (pintype "passive"))
      (node (ref "SW27") (pin "1") (pinfunction "1_1") (pintype "passive"))
      (node (ref "SW44") (pin "1") (pinfunction "1_1") (pintype "passive"))
      (node (ref "SW61") (pin "1") (pinfunction "1_1") (pintype "passive"))
      (node (ref "SW74") (pin "1") (pinfunction "1_1") (pintype "passive"))
      (node (ref "SW81") (pin "1") (pinfunction "1_1") (pintype "passive"))
      (node (ref "U1") (pin "29") (pinfunction "PB10_29") (pintype "bidirectional"))
    )
    (net (code "13") (name "/Col12") (class "Default")
      (node (ref "SW11") (pin "1") (pinfunction "1_1") (pintype "passive"))
      (node (ref "SW28") (pin "1") (pinfunction "1_1") (pintype "passive"))
      (node (ref "SW45") (pin "1") (pinfunction "1_1") (pintype "passive"))
      (node (ref "SW62") (pin "1") (pinfunction "1_1") (pintype "passive"))
      (node (ref "SW75") (pin "1") (pinfunction "1_1") (pintype "passive"))
      (node (ref "SW82") (pin "1") (pinfunction "1_1") (pintype "passive"))
      (node (ref "U1") (pin "30") (pinfunction "PB11_30") (pintype "bidirectional"))
    )
    (net (code "14") (name "/Col13") (class "Default")
      (node (ref "SW12") (pin "1") (pinfunction "1_1") (pintype "passive"))
      (node (ref "SW29") (pin "1") (pinfunction "1_1") (pintype "passive"))
      (node (ref "SW46") (pin "1") (pinfunction "1_1") (pintype "passive"))
      (node (ref "SW63") (pin "1") (pinfunction "1_1") (pintype "passive"))
      (node (ref "SW83") (pin "1") (pinfunction "1_1") (pintype "passive"))
      (node (ref "U1") (pin "33") (pinfunction "PB12_33") (pintype "bidirectional"))
    )
    (net (code "15") (name "/Col14") (class "Default")
      (node (ref "SW13") (pin "1") (pinfunction "1_1") (pintype "passive"))
      (node (ref "SW16") (pin "1") (pinfunction "1_1") (pintype "passive"))
      (node (ref "SW30") (pin "1") (pinfunction "1_1") (pintype "passive"))
      (node (ref "SW47") (pin "1") (pinfunction "1_1") (pintype "passive"))
      (node (ref "SW84") (pin "1") (pinfunction "1_1") (pintype "passive"))
      (node (ref "U1") (pin "34") (pinfunction "PB13_34") (pintype "bidirectional"))
    )
    (net (code "16") (name "/Col15") (class "Default")
      (node (ref "SW14") (pin "1") (pinfunction "1_1") (pintype "passive"))
      (node (ref "SW31") (pin "1") (pinfunction "1_1") (pintype "passive"))
      (node (ref "SW33") (pin "1") (pinfunction "1_1") (pintype "passive"))
      (node (ref "SW48") (pin "1") (pinfunction "1_1") (pintype "passive"))
      (node (ref "SW85") (pin "1") (pinfunction "1_1") (pintype "passive"))
      (node (ref "SW87") (pin "1") (pinfunction "1_1") (pintype "passive"))
      (node (ref "U1") (pin "35") (pinfunction "PB14_35") (pintype "bidirectional"))
    )
    (net (code "17") (name "/Col16") (class "Default")
      (node (ref "SW15") (pin "1") (pinfunction "1_1") (pintype "passive"))
      (node (ref "SW32") (pin "1") (pinfunction "1_1") (pintype "passive"))
      (node (ref "SW49") (pin "1") (pinfunction "1_1") (pintype "passive"))
      (node (ref "SW50") (pin "1") (pinfunction "1_1") (pintype "passive"))
      (node (ref "SW76") (pin "1") (pinfunction "1_1") (pintype "passive"))
      (node (ref "SW86") (pin "1") (pinfunction "1_1") (pintype "passive"))
      (node (ref "U1") (pin "36") (pinfunction "PB15_36") (pintype "bidirectional"))
    )
    (net (code "18") (name "/JTCK") (class "Default")
      (node (ref "JP6") (pin "3") (pinfunction "3_3") (pintype "passive"))
      (node (ref "U1") (pin "46") (pinfunction "PA13_46") (pintype "bidirectional"))
    )
    (net (code "19") (name "/JTMS") (class "Default")
      (node (ref "JP6") (pin "4") (pinfunction "4_4") (pintype "passive"))
      (node (ref "U1") (pin "49") (pinfunction "PA14_49") (pintype "bidirectional"))
    )
    (net (code "20") (name "/LED_Caps") (class "Default")
      (node (ref "D89") (pin "K") (pinfunction "K_K") (pintype "passive"))
      (node (ref "U1") (pin "14") (pinfunction "PA0-WKUP_14") (pintype "bidirectional"))
    )
    (net (code "21") (name "/LED_ScrLk") (class "Default")
      (node (ref "D90") (pin "K") (pinfunction "K_K") (pintype "passive"))
      (node (ref "U1") (pin "15") (pinfunction "PA1_15") (pintype "bidirectional"))
    )
    (net (code "22") (name "/OSC_IN") (class "Default")
      (node (ref "C11") (pin "1") (pinfunction "1_1") (pintype "passive"))
      (node (ref "U1") (pin "5") (pinfunction "PD0-OSC_IN_5") (pintype "bidirectional"))
      (node (ref "Y1") (pin "2") (pinfunction "OSC2_2") (pintype "passive"))
    )
    (net (code "23") (name "/OSC_OUT") (class "Default")
      (node (ref "C12") (pin "1") (pinfunction "1_1") (pintype "passive"))
      (node (ref "U1") (pin "6") (pinfunction "PD1_6") (pintype "bidirectional"))
      (node (ref "Y1") (pin "1") (pinfunction "OSC1_1") (pintype "passive"))
    )
    (net (code "24") (name "/PA2") (class "Default")
      (node (ref "U1") (pin "16") (pinfunction "PA2_16") (pintype "bidirectional"))
    )
    (net (code "25") (name "/PA3") (class "Default")
      (node (ref "U1") (pin "17") (pinfunction "PA3_17") (pintype "bidirectional"))
    )
    (net (code "26") (name "/PA4") (class "Default")
      (node (ref "U1") (pin "20") (pinfunction "PA4_20") (pintype "bidirectional"))
    )
    (net (code "27") (name "/PA5") (class "Default")
      (node (ref "U1") (pin "21") (pinfunction "PA5_21") (pintype "bidirectional"))
    )
    (net (code "28") (name "/PA6") (class "Default")
      (node (ref "U1") (pin "22") (pinfunction "PA6_22") (pintype "bidirectional"))
    )
    (net (code "29") (name "/PA7") (class "Default")
      (node (ref "U1") (pin "23") (pinfunction "PA7_23") (pintype "bidirectional"))
    )
    (net (code "30") (name "/PA8") (class "Default")
      (node (ref "U1") (pin "41") (pinfunction "PA8_41") (pintype "bidirectional"))
    )
    (net (code "31") (name "/PA9") (class "Default")
      (node (ref "U1") (pin "42") (pinfunction "PA9_42") (pintype "bidirectional"))
    )
    (net (code "32") (name "/PA10") (class "Default")
      (node (ref "U1") (pin "43") (pinfunction "PA10_43") (pintype "bidirectional"))
    )
    (net (code "33") (name "/PA15") (class "Default")
      (node (ref "U1") (pin "50") (pinfunction "PA15_50") (pintype "bidirectional"))
    )
    (net (code "34") (name "/PC6") (class "Default")
      (node (ref "U1") (pin "37") (pinfunction "PC6_37") (pintype "bidirectional"))
    )
    (net (code "35") (name "/PC7") (class "Default")
      (node (ref "U1") (pin "38") (pinfunction "PC7_38") (pintype "bidirectional"))
    )
    (net (code "36") (name "/PC8") (class "Default")
      (node (ref "U1") (pin "39") (pinfunction "PC8_39") (pintype "bidirectional"))
    )
    (net (code "37") (name "/PC9") (class "Default")
      (node (ref "U1") (pin "40") (pinfunction "PC9_40") (pintype "bidirectional"))
    )
    (net (code "38") (name "/PC10") (class "Default")
      (node (ref "U1") (pin "51") (pinfunction "PC10_51") (pintype "bidirectional"))
    )
    (net (code "39") (name "/PC11") (class "Default")
      (node (ref "U1") (pin "52") (pinfunction "PC11_52") (pintype "bidirectional"))
    )
    (net (code "40") (name "/PC12") (class "Default")
      (node (ref "U1") (pin "53") (pinfunction "PC12_53") (pintype "bidirectional"))
    )
    (net (code "41") (name "/PC13") (class "Default")
      (node (ref "U1") (pin "2") (pinfunction "PC13-TAMPER-RTC_2") (pintype "bidirectional"))
    )
    (net (code "42") (name "/PC14") (class "Default")
      (node (ref "U1") (pin "3") (pinfunction "PC14-OSC32_IN_3") (pintype "bidirectional"))
    )
    (net (code "43") (name "/PC15") (class "Default")
      (node (ref "U1") (pin "4") (pinfunction "PC15-OSC32_OUT_4") (pintype "bidirectional"))
    )
    (net (code "44") (name "/PD2") (class "Default")
      (node (ref "U1") (pin "54") (pinfunction "PD2_54") (pintype "bidirectional"))
    )
    (net (code "45") (name "/RST") (class "Default")
      (node (ref "C13") (pin "1") (pinfunction "1_1") (pintype "passive"))
      (node (ref "R4") (pin "1") (pinfunction "1_1") (pintype "passive"))
      (node (ref "U1") (pin "7") (pinfunction "NRST_7") (pintype "bidirectional"))
    )
    (net (code "46") (name "/Row1") (class "Default")
      (node (ref "D1") (pin "1") (pinfunction "A_1") (pintype "passive"))
      (node (ref "D10") (pin "1") (pinfunction "A_1") (pintype "passive"))
      (node (ref "D11") (pin "1") (pinfunction "A_1") (pintype "passive"))
      (node (ref "D12") (pin "1") (pinfunction "A_1") (pintype "passive"))
      (node (ref "D13") (pin "1") (pinfunction "A_1") (pintype "passive"))
      (node (ref "D14") (pin "1") (pinfunction "A_1") (pintype "passive"))
      (node (ref "D15") (pin "1") (pinfunction "A_1") (pintype "passive"))
      (node (ref "D2") (pin "1") (pinfunction "A_1") (pintype "passive"))
      (node (ref "D3") (pin "1") (pinfunction "A_1") (pintype "passive"))
      (node (ref "D4") (pin "1") (pinfunction "A_1") (pintype "passive"))
      (node (ref "D5") (pin "1") (pinfunction "A_1") (pintype "passive"))
      (node (ref "D6") (pin "1") (pinfunction "A_1") (pintype "passive"))
      (node (ref "D7") (pin "1") (pinfunction "A_1") (pintype "passive"))
      (node (ref "D8") (pin "1") (pinfunction "A_1") (pintype "passive"))
      (node (ref "D9") (pin "1") (pinfunction "A_1") (pintype "passive"))
      (node (ref "U1") (pin "8") (pinfunction "PC0_8") (pintype "bidirectional"))
    )
    (net (code "47") (name "/Row2") (class "Default")
      (node (ref "D17") (pin "1") (pinfunction "A_1") (pintype "passive"))
      (node (ref "D18") (pin "1") (pinfunction "A_1") (pintype "passive"))
      (node (ref "D19") (pin "1") (pinfunction "A_1") (pintype "passive"))
      (node (ref "D20") (pin "1") (pinfunction "A_1") (pintype "passive"))
      (node (ref "D21") (pin "1") (pinfunction "A_1") (pintype "passive"))
      (node (ref "D22") (pin "1") (pinfunction "A_1") (pintype "passive"))
      (node (ref "D23") (pin "1") (pinfunction "A_1") (pintype "passive"))
      (node (ref "D24") (pin "1") (pinfunction "A_1") (pintype "passive"))
      (node (ref "D25") (pin "1") (pinfunction "A_1") (pintype "passive"))
      (node (ref "D26") (pin "1") (pinfunction "A_1") (pintype "passive"))
      (node (ref "D27") (pin "1") (pinfunction "A_1") (pintype "passive"))
      (node (ref "D28") (pin "1") (pinfunction "A_1") (pintype "passive"))
      (node (ref "D29") (pin "1") (pinfunction "A_1") (pintype "passive"))
      (node (ref "D30") (pin "1") (pinfunction "A_1") (pintype "passive"))
      (node (ref "D31") (pin "1") (pinfunction "A_1") (pintype "passive"))
      (node (ref "D32") (pin "1") (pinfunction "A_1") (pintype "passive"))
      (node (ref "U1") (pin "9") (pinfunction "PC1_9") (pintype "bidirectional"))
    )
    (net (code "48") (name "/Row3") (class "Default")
      (node (ref "D34") (pin "1") (pinfunction "A_1") (pintype "passive"))
      (node (ref "D35") (pin "1") (pinfunction "A_1") (pintype "passive"))
      (node (ref "D36") (pin "1") (pinfunction "A_1") (pintype "passive"))
      (node (ref "D37") (pin "1") (pinfunction "A_1") (pintype "passive"))
      (node (ref "D38") (pin "1") (pinfunction "A_1") (pintype "passive"))
      (node (ref "D39") (pin "1") (pinfunction "A_1") (pintype "passive"))
      (node (ref "D40") (pin "1") (pinfunction "A_1") (pintype "passive"))
      (node (ref "D41") (pin "1") (pinfunction "A_1") (pintype "passive"))
      (node (ref "D42") (pin "1") (pinfunction "A_1") (pintype "passive"))
      (node (ref "D43") (pin "1") (pinfunction "A_1") (pintype "passive"))
      (node (ref "D44") (pin "1") (pinfunction "A_1") (pintype "passive"))
      (node (ref "D45") (pin "1") (pinfunction "A_1") (pintype "passive"))
      (node (ref "D46") (pin "1") (pinfunction "A_1") (pintype "passive"))
      (node (ref "D47") (pin "1") (pinfunction "A_1") (pintype "passive"))
      (node (ref "D48") (pin "1") (pinfunction "A_1") (pintype "passive"))
      (node (ref "D49") (pin "1") (pinfunction "A_1") (pintype "passive"))
      (node (ref "U1") (pin "10") (pinfunction "PC2_10") (pintype "bidirectional"))
    )
    (net (code "49") (name "/Row4") (class "Default")
      (node (ref "D16") (pin "1") (pinfunction "A_1") (pintype "passive"))
      (node (ref "D33") (pin "1") (pinfunction "A_1") (pintype "passive"))
      (node (ref "D50") (pin "1") (pinfunction "A_1") (pintype "passive"))
      (node (ref "D51") (pin "1") (pinfunction "A_1") (pintype "passive"))
      (node (ref "D52") (pin "1") (pinfunction "A_1") (pintype "passive"))
      (node (ref "D53") (pin "1") (pinfunction "A_1") (pintype "passive"))
      (node (ref "D54") (pin "1") (pinfunction "A_1") (pintype "passive"))
      (node (ref "D55") (pin "1") (pinfunction "A_1") (pintype "passive"))
      (node (ref "D56") (pin "1") (pinfunction "A_1") (pintype "passive"))
      (node (ref "D57") (pin "1") (pinfunction "A_1") (pintype "passive"))
      (node (ref "D58") (pin "1") (pinfunction "A_1") (pintype "passive"))
      (node (ref "D59") (pin "1") (pinfunction "A_1") (pintype "passive"))
      (node (ref "D60") (pin "1") (pinfunction "A_1") (pintype "passive"))
      (node (ref "D61") (pin "1") (pinfunction "A_1") (pintype "passive"))
      (node (ref "D62") (pin "1") (pinfunction "A_1") (pintype "passive"))
      (node (ref "D63") (pin "1") (pinfunction "A_1") (pintype "passive"))
      (node (ref "U1") (pin "11") (pinfunction "PC3_11") (pintype "bidirectional"))
    )
    (net (code "50") (name "/Row5") (class "Default")
      (node (ref "D64") (pin "1") (pinfunction "A_1") (pintype "passive"))
      (node (ref "D65") (pin "1") (pinfunction "A_1") (pintype "passive"))
      (node (ref "D66") (pin "1") (pinfunction "A_1") (pintype "passive"))
      (node (ref "D67") (pin "1") (pinfunction "A_1") (pintype "passive"))
      (node (ref "D68") (pin "1") (pinfunction "A_1") (pintype "passive"))
      (node (ref "D69") (pin "1") (pinfunction "A_1") (pintype "passive"))
      (node (ref "D70") (pin "1") (pinfunction "A_1") (pintype "passive"))
      (node (ref "D71") (pin "1") (pinfunction "A_1") (pintype "passive"))
      (node (ref "D72") (pin "1") (pinfunction "A_1") (pintype "passive"))
      (node (ref "D73") (pin "1") (pinfunction "A_1") (pintype "passive"))
      (node (ref "D74") (pin "1") (pinfunction "A_1") (pintype "passive"))
      (node (ref "D75") (pin "1") (pinfunction "A_1") (pintype "passive"))
      (node (ref "D76") (pin "1") (pinfunction "A_1") (pintype "passive"))
      (node (ref "D87") (pin "1") (pinfunction "A_1") (pintype "passive"))
      (node (ref "U1") (pin "24") (pinfunction "PC4_24") (pintype "bidirectional"))
    )
    (net (code "51") (name "/Row6") (class "Default")
      (node (ref "D77") (pin "1") (pinfunction "A_1") (pintype "passive"))
      (node (ref "D78") (pin "1") (pinfunction "A_1") (pintype "passive"))
      (node (ref "D79") (pin "1") (pinfunction "A_1") (pintype "passive"))
      (node (ref "D80") (pin "1") (pinfunction "A_1") (pintype "passive"))
      (node (ref "D81") (pin "1") (pinfunction "A_1") (pintype "passive"))
      (node (ref "D82") (pin "1") (pinfunction "A_1") (pintype "passive"))
      (node (ref "D83") (pin "1") (pinfunction "A_1") (pintype "passive"))
      (node (ref "D84") (pin "1") (pinfunction "A_1") (pintype "passive"))
      (node (ref "D85") (pin "1") (pinfunction "A_1") (pintype "passive"))
      (node (ref "D86") (pin "1") (pinfunction "A_1") (pintype "passive"))
      (node (ref "U1") (pin "25") (pinfunction "PC5_25") (pintype "bidirectional"))
    )
    (net (code "52") (name "/USB_D+") (class "Default")
      (node (ref "J1") (pin "6") (pinfunction "A6___DP1_6") (pintype "passive"))
      (node (ref "J1") (pin "8") (pinfunction "B6___DP2_8") (pintype "passive"))
      (node (ref "U1") (pin "45") (pinfunction "PA12_45") (pintype "bidirectional"))
    )
    (net (code "53") (name "/USB_D-") (class "Default")
      (node (ref "J1") (pin "5") (pinfunction "B7___DN2_5") (pintype "passive"))
      (node (ref "J1") (pin "7") (pinfunction "A7___DN1_7") (pintype "passive"))
      (node (ref "U1") (pin "44") (pinfunction "PA11_44") (pintype "bidirectional"))
    )
    (net (code "54") (name "3.3V") (class "Default")
      (node (ref "C10") (pin "2") (pinfunction "2_2") (pintype "passive"))
      (node (ref "C2") (pin "1") (pinfunction "1_1") (pintype "passive"))
      (node (ref "C3") (pin "2") (pinfunction "2_2") (pintype "passive"))
      (node (ref "C4") (pin "2") (pinfunction "2_2") (pintype "passive"))
      (node (ref "C5") (pin "2") (pinfunction "2_2") (pintype "passive"))
      (node (ref "C6") (pin "2") (pinfunction "2_2") (pintype "passive"))
      (node (ref "C7") (pin "2") (pinfunction "2_2") (pintype "passive"))
      (node (ref "C8") (pin "2") (pinfunction "2_2") (pintype "passive"))
      (node (ref "C9") (pin "2") (pinfunction "2_2") (pintype "passive"))
      (node (ref "JP6") (pin "1") (pinfunction "1_1") (pintype "passive"))
      (node (ref "R2") (pin "1") (pinfunction "1_1") (pintype "passive"))
      (node (ref "R3") (pin "1") (pinfunction "1_1") (pintype "passive"))
      (node (ref "R4") (pin "2") (pinfunction "2_2") (pintype "passive"))
      (node (ref "U1") (pin "1") (pinfunction "VBAT_1") (pintype "power_in"))
      (node (ref "U1") (pin "13") (pinfunction "VDDA_13") (pintype "power_in"))
      (node (ref "U1") (pin "19") (pinfunction "VDD_4_19") (pintype "power_in"))
      (node (ref "U1") (pin "32") (pinfunction "VDD_1_32") (pintype "power_in"))
      (node (ref "U1") (pin "48") (pinfunction "VDD_2_48") (pintype "power_in"))
      (node (ref "U1") (pin "64") (pinfunction "VDD_3_64") (pintype "power_in"))
      (node (ref "VR1") (pin "2") (pinfunction "Vout_2") (pintype "passive"))
    )
    (net (code "55") (name "5V") (class "Default")
      (node (ref "C1") (pin "1") (pinfunction "1_1") (pintype "passive"))
      (node (ref "J1") (pin "11") (pinfunction "B4___VBUS_11") (pintype "passive"))
      (node (ref "J1") (pin "2") (pinfunction "A4___VBUS_2") (pintype "passive"))
      (node (ref "R1") (pin "1") (pinfunction "1_1") (pintype "passive"))
      (node (ref "VR1") (pin "3") (pinfunction "Vin_3") (pintype "passive"))
    )
    (net (code "56") (name "GND") (class "Default")
      (node (ref "C1") (pin "2") (pinfunction "2_2") (pintype "passive"))
      (node (ref "C10") (pin "1") (pinfunction "1_1") (pintype "passive"))
      (node (ref "C11") (pin "2") (pinfunction "2_2") (pintype "passive"))
      (node (ref "C12") (pin "2") (pinfunction "2_2") (pintype "passive"))
      (node (ref "C13") (pin "2") (pinfunction "2_2") (pintype "passive"))
      (node (ref "C2") (pin "2") (pinfunction "2_2") (pintype "passive"))
      (node (ref "C3") (pin "1") (pinfunction "1_1") (pintype "passive"))
      (node (ref "C4") (pin "1") (pinfunction "1_1") (pintype "passive"))
      (node (ref "C5") (pin "1") (pinfunction "1_1") (pintype "passive"))
      (node (ref "C6") (pin "1") (pinfunction "1_1") (pintype "passive"))
      (node (ref "C7") (pin "1") (pinfunction "1_1") (pintype "passive"))
      (node (ref "C8") (pin "1") (pinfunction "1_1") (pintype "passive"))
      (node (ref "C9") (pin "1") (pinfunction "1_1") (pintype "passive"))
      (node (ref "D88") (pin "K") (pinfunction "K_K") (pintype "passive"))
      (node (ref "J1") (pin "1") (pinfunction "B12_GND_1") (pintype "passive"))
      (node (ref "J1") (pin "12") (pinfunction "B1___GND_12") (pintype "passive"))
      (node (ref "JP6") (pin "2") (pinfunction "2_2") (pintype "passive"))
      (node (ref "R5") (pin "2") (pinfunction "2_2") (pintype "passive"))
      (node (ref "R6") (pin "1") (pinfunction "1_1") (pintype "passive"))
      (node (ref "R7") (pin "1") (pinfunction "1_1") (pintype "passive"))
      (node (ref "U1") (pin "12") (pinfunction "VSSA_12") (pintype "power_in"))
      (node (ref "U1") (pin "18") (pinfunction "VSS_4_18") (pintype "power_in"))
      (node (ref "U1") (pin "31") (pinfunction "VSS_1_31") (pintype "power_in"))
      (node (ref "U1") (pin "47") (pinfunction "VSS_2_47") (pintype "power_in"))
      (node (ref "U1") (pin "63") (pinfunction "VSS_3_63") (pintype "power_in"))
      (node (ref "VR1") (pin "1") (pinfunction "GND_1") (pintype "passive"))
    )
    (net (code "57") (name "Net-(D1-K)") (class "Default")
      (node (ref "D1") (pin "2") (pinfunction "K_2") (pintype "passive"))
      (node (ref "SW1") (pin "2") (pinfunction "2_2") (pintype "passive"))
    )
    (net (code "58") (name "Net-(D2-K)") (class "Default")
      (node (ref "D2") (pin "2") (pinfunction "K_2") (pintype "passive"))
      (node (ref "SW2") (pin "2") (pinfunction "2_2") (pintype "passive"))
    )
    (net (code "59") (name "Net-(D3-K)") (class "Default")
      (node (ref "D3") (pin "2") (pinfunction "K_2") (pintype "passive"))
      (node (ref "SW3") (pin "2") (pinfunction "2_2") (pintype "passive"))
    )
    (net (code "60") (name "Net-(D4-K)") (class "Default")
      (node (ref "D4") (pin "2") (pinfunction "K_2") (pintype "passive"))
      (node (ref "SW4") (pin "2") (pinfunction "2_2") (pintype "passive"))
    )
    (net (code "61") (name "Net-(D5-K)") (class "Default")
      (node (ref "D5") (pin "2") (pinfunction "K_2") (pintype "passive"))
      (node (ref "SW5") (pin "2") (pinfunction "2_2") (pintype "passive"))
    )
    (net (code "62") (name "Net-(D6-K)") (class "Default")
      (node (ref "D6") (pin "2") (pinfunction "K_2") (pintype "passive"))
      (node (ref "SW6") (pin "2") (pinfunction "2_2") (pintype "passive"))
    )
    (net (code "63") (name "Net-(D7-K)") (class "Default")
      (node (ref "D7") (pin "2") (pinfunction "K_2") (pintype "passive"))
      (node (ref "SW7") (pin "2") (pinfunction "2_2") (pintype "passive"))
    )
    (net (code "64") (name "Net-(D8-K)") (class "Default")
      (node (ref "D8") (pin "2") (pinfunction "K_2") (pintype "passive"))
      (node (ref "SW8") (pin "2") (pinfunction "2_2") (pintype "passive"))
    )
    (net (code "65") (name "Net-(D9-K)") (class "Default")
      (node (ref "D9") (pin "2") (pinfunction "K_2") (pintype "passive"))
      (node (ref "SW9") (pin "2") (pinfunction "2_2") (pintype "passive"))
    )
    (net (code "66") (name "Net-(D10-K)") (class "Default")
      (node (ref "D10") (pin "2") (pinfunction "K_2") (pintype "passive"))
      (node (ref "SW10") (pin "2") (pinfunction "2_2") (pintype "passive"))
    )
    (net (code "67") (name "Net-(D11-K)") (class "Default")
      (node (ref "D11") (pin "2") (pinfunction "K_2") (pintype "passive"))
      (node (ref "SW11") (pin "2") (pinfunction "2_2") (pintype "passive"))
    )
    (net (code "68") (name "Net-(D12-K)") (class "Default")
      (node (ref "D12") (pin "2") (pinfunction "K_2") (pintype "passive"))
      (node (ref "SW12") (pin "2") (pinfunction "2_2") (pintype "passive"))
    )
    (net (code "69") (name "Net-(D13-K)") (class "Default")
      (node (ref "D13") (pin "2") (pinfunction "K_2") (pintype "passive"))
      (node (ref "SW13") (pin "2") (pinfunction "2_2") (pintype "passive"))
    )
    (net (code "70") (name "Net-(D14-K)") (class "Default")
      (node (ref "D14") (pin "2") (pinfunction "K_2") (pintype "passive"))
      (node (ref "SW14") (pin "2") (pinfunction "2_2") (pintype "passive"))
    )
    (net (code "71") (name "Net-(D15-K)") (class "Default")
      (node (ref "D15") (pin "2") (pinfunction "K_2") (pintype "passive"))
      (node (ref "SW15") (pin "2") (pinfunction "2_2") (pintype "passive"))
    )
    (net (code "72") (name "Net-(D16-K)") (class "Default")
      (node (ref "D16") (pin "2") (pinfunction "K_2") (pintype "passive"))
      (node (ref "SW16") (pin "2") (pinfunction "2_2") (pintype "passive"))
    )
    (net (code "73") (name "Net-(D17-K)") (class "Default")
      (node (ref "D17") (pin "2") (pinfunction "K_2") (pintype "passive"))
      (node (ref "SW17") (pin "2") (pinfunction "2_2") (pintype "passive"))
    )
    (net (code "74") (name "Net-(D18-K)") (class "Default")
      (node (ref "D18") (pin "2") (pinfunction "K_2") (pintype "passive"))
      (node (ref "SW18") (pin "2") (pinfunction "2_2") (pintype "passive"))
    )
    (net (code "75") (name "Net-(D19-K)") (class "Default")
      (node (ref "D19") (pin "2") (pinfunction "K_2") (pintype "passive"))
      (node (ref "SW19") (pin "2") (pinfunction "2_2") (pintype "passive"))
    )
    (net (code "76") (name "Net-(D20-K)") (class "Default")
      (node (ref "D20") (pin "2") (pinfunction "K_2") (pintype "passive"))
      (node (ref "SW20") (pin "2") (pinfunction "2_2") (pintype "passive"))
    )
    (net (code "77") (name "Net-(D21-K)") (class "Default")
      (node (ref "D21") (pin "2") (pinfunction "K_2") (pintype "passive"))
      (node (ref "SW21") (pin "2") (pinfunction "2_2") (pintype "passive"))
    )
    (net (code "78") (name "Net-(D22-K)") (class "Default")
      (node (ref "D22") (pin "2") (pinfunction "K_2") (pintype "passive"))
      (node (ref "SW22") (pin "2") (pinfunction "2_2") (pintype "passive"))
    )
    (net (code "79") (name "Net-(D23-K)") (class "Default")
      (node (ref "D23") (pin "2") (pinfunction "K_2") (pintype "passive"))
      (node (ref "SW23") (pin "2") (pinfunction "2_2") (pintype "passive"))
    )
    (net (code "80") (name "Net-(D24-K)") (class "Default")
      (node (ref "D24") (pin "2") (pinfunction "K_2") (pintype "passive"))
      (node (ref "SW24") (pin "2") (pinfunction "2_2") (pintype "passive"))
    )
    (net (code "81") (name "Net-(D25-K)") (class "Default")
      (node (ref "D25") (pin "2") (pinfunction "K_2") (pintype "passive"))
      (node (ref "SW25") (pin "2") (pinfunction "2_2") (pintype "passive"))
    )
    (net (code "82") (name "Net-(D26-K)") (class "Default")
      (node (ref "D26") (pin "2") (pinfunction "K_2") (pintype "passive"))
      (node (ref "SW26") (pin "2") (pinfunction "2_2") (pintype "passive"))
    )
    (net (code "83") (name "Net-(D27-K)") (class "Default")
      (node (ref "D27") (pin "2") (pinfunction "K_2") (pintype "passive"))
      (node (ref "SW27") (pin "2") (pinfunction "2_2") (pintype "passive"))
    )
    (net (code "84") (name "Net-(D28-K)") (class "Default")
      (node (ref "D28") (pin "2") (pinfunction "K_2") (pintype "passive"))
      (node (ref "SW28") (pin "2") (pinfunction "2_2") (pintype "passive"))
    )
    (net (code "85") (name "Net-(D29-K)") (class "Default")
      (node (ref "D29") (pin "2") (pinfunction "K_2") (pintype "passive"))
      (node (ref "SW29") (pin "2") (pinfunction "2_2") (pintype "passive"))
    )
    (net (code "86") (name "Net-(D30-K)") (class "Default")
      (node (ref "D30") (pin "2") (pinfunction "K_2") (pintype "passive"))
      (node (ref "SW30") (pin "2") (pinfunction "2_2") (pintype "passive"))
    )
    (net (code "87") (name "Net-(D31-K)") (class "Default")
      (node (ref "D31") (pin "2") (pinfunction "K_2") (pintype "passive"))
      (node (ref "SW31") (pin "2") (pinfunction "2_2") (pintype "passive"))
    )
    (net (code "88") (name "Net-(D32-K)") (class "Default")
      (node (ref "D32") (pin "2") (pinfunction "K_2") (pintype "passive"))
      (node (ref "SW32") (pin "2") (pinfunction "2_2") (pintype "passive"))
    )
    (net (code "89") (name "Net-(D33-K)") (class "Default")
      (node (ref "D33") (pin "2") (pinfunction "K_2") (pintype "passive"))
      (node (ref "SW33") (pin "2") (pinfunction "2_2") (pintype "passive"))
    )
    (net (code "90") (name "Net-(D34-K)") (class "Default")
      (node (ref "D34") (pin "2") (pinfunction "K_2") (pintype "passive"))
      (node (ref "SW34") (pin "2") (pinfunction "2_2") (pintype "passive"))
    )
    (net (code "91") (name "Net-(D35-K)") (class "Default")
      (node (ref "D35") (pin "2") (pinfunction "K_2") (pintype "passive"))
      (node (ref "SW35") (pin "2") (pinfunction "2_2") (pintype "passive"))
    )
    (net (code "92") (name "Net-(D36-K)") (class "Default")
      (node (ref "D36") (pin "2") (pinfunction "K_2") (pintype "passive"))
      (node (ref "SW36") (pin "2") (pinfunction "2_2") (pintype "passive"))
    )
    (net (code "93") (name "Net-(D37-K)") (class "Default")
      (node (ref "D37") (pin "2") (pinfunction "K_2") (pintype "passive"))
      (node (ref "SW37") (pin "2") (pinfunction "2_2") (pintype "passive"))
    )
    (net (code "94") (name "Net-(D38-K)") (class "Default")
      (node (ref "D38") (pin "2") (pinfunction "K_2") (pintype "passive"))
      (node (ref "SW38") (pin "2") (pinfunction "2_2") (pintype "passive"))
    )
    (net (code "95") (name "Net-(D39-K)") (class "Default")
      (node (ref "D39") (pin "2") (pinfunction "K_2") (pintype "passive"))
      (node (ref "SW39") (pin "2") (pinfunction "2_2") (pintype "passive"))
    )
    (net (code "96") (name "Net-(D40-K)") (class "Default")
      (node (ref "D40") (pin "2") (pinfunction "K_2") (pintype "passive"))
      (node (ref "SW40") (pin "2") (pinfunction "2_2") (pintype "passive"))
    )
    (net (code "97") (name "Net-(D41-K)") (class "Default")
      (node (ref "D41") (pin "2") (pinfunction "K_2") (pintype "passive"))
      (node (ref "SW41") (pin "2") (pinfunction "2_2") (pintype "passive"))
    )
    (net (code "98") (name "Net-(D42-K)") (class "Default")
      (node (ref "D42") (pin "2") (pinfunction "K_2") (pintype "passive"))
      (node (ref "SW42") (pin "2") (pinfunction "2_2") (pintype "passive"))
    )
    (net (code "99") (name "Net-(D43-K)") (class "Default")
      (node (ref "D43") (pin "2") (pinfunction "K_2") (pintype "passive"))
      (node (ref "SW43") (pin "2") (pinfunction "2_2") (pintype "passive"))
    )
    (net (code "100") (name "Net-(D44-K)") (class "Default")
      (node (ref "D44") (pin "2") (pinfunction "K_2") (pintype "passive"))
      (node (ref "SW44") (pin "2") (pinfunction "2_2") (pintype "passive"))
    )
    (net (code "101") (name "Net-(D45-K)") (class "Default")
      (node (ref "D45") (pin "2") (pinfunction "K_2") (pintype "passive"))
      (node (ref "SW45") (pin "2") (pinfunction "2_2") (pintype "passive"))
    )
    (net (code "102") (name "Net-(D46-K)") (class "Default")
      (node (ref "D46") (pin "2") (pinfunction "K_2") (pintype "passive"))
      (node (ref "SW46") (pin "2") (pinfunction "2_2") (pintype "passive"))
    )
    (net (code "103") (name "Net-(D47-K)") (class "Default")
      (node (ref "D47") (pin "2") (pinfunction "K_2") (pintype "passive"))
      (node (ref "SW47") (pin "2") (pinfunction "2_2") (pintype "passive"))
    )
    (net (code "104") (name "Net-(D48-K)") (class "Default")
      (node (ref "D48") (pin "2") (pinfunction "K_2") (pintype "passive"))
      (node (ref "SW48") (pin "2") (pinfunction "2_2") (pintype "passive"))
    )
    (net (code "105") (name "Net-(D49-K)") (class "Default")
      (node (ref "D49") (pin "2") (pinfunction "K_2") (pintype "passive"))
      (node (ref "SW49") (pin "2") (pinfunction "2_2") (pintype "passive"))
    )
    (net (code "106") (name "Net-(D50-K)") (class "Default")
      (node (ref "D50") (pin "2") (pinfunction "K_2") (pintype "passive"))
      (node (ref "SW50") (pin "2") (pinfunction "2_2") (pintype "passive"))
    )
    (net (code "107") (name "Net-(D51-K)") (class "Default")
      (node (ref "D51") (pin "2") (pinfunction "K_2") (pintype "passive"))
      (node (ref "SW51") (pin "2") (pinfunction "2_2") (pintype "passive"))
    )
    (net (code "108") (name "Net-(D52-K)") (class "Default")
      (node (ref "D52") (pin "2") (pinfunction "K_2") (pintype "passive"))
      (node (ref "SW52") (pin "2") (pinfunction "2_2") (pintype "passive"))
    )
    (net (code "109") (name "Net-(D53-K)") (class "Default")
      (node (ref "D53") (pin "2") (pinfunction "K_2") (pintype "passive"))
      (node (ref "SW53") (pin "2") (pinfunction "2_2") (pintype "passive"))
    )
    (net (code "110") (name "Net-(D54-K)") (class "Default")
      (node (ref "D54") (pin "2") (pinfunction "K_2") (pintype "passive"))
      (node (ref "SW54") (pin "2") (pinfunction "2_2") (pintype "passive"))
    )
    (net (code "111") (name "Net-(D55-K)") (class "Default")
      (node (ref "D55") (pin "2") (pinfunction "K_2") (pintype "passive"))
      (node (ref "SW55") (pin "2") (pinfunction "2_2") (pintype "passive"))
    )
    (net (code "112") (name "Net-(D56-K)") (class "Default")
      (node (ref "D56") (pin "2") (pinfunction "K_2") (pintype "passive"))
      (node (ref "SW56") (pin "2") (pinfunction "2_2") (pintype "passive"))
    )
    (net (code "113") (name "Net-(D57-K)") (class "Default")
      (node (ref "D57") (pin "2") (pinfunction "K_2") (pintype "passive"))
      (node (ref "SW57") (pin "2") (pinfunction "2_2") (pintype "passive"))
    )
    (net (code "114") (name "Net-(D58-K)") (class "Default")
      (node (ref "D58") (pin "2") (pinfunction "K_2") (pintype "passive"))
      (node (ref "SW58") (pin "2") (pinfunction "2_2") (pintype "passive"))
    )
    (net (code "115") (name "Net-(D59-K)") (class "Default")
      (node (ref "D59") (pin "2") (pinfunction "K_2") (pintype "passive"))
      (node (ref "SW59") (pin "2") (pinfunction "2_2") (pintype "passive"))
    )
    (net (code "116") (name "Net-(D60-K)") (class "Default")
      (node (ref "D60") (pin "2") (pinfunction "K_2") (pintype "passive"))
      (node (ref "SW60") (pin "2") (pinfunction "2_2") (pintype "passive"))
    )
    (net (code "117") (name "Net-(D61-K)") (class "Default")
      (node (ref "D61") (pin "2") (pinfunction "K_2") (pintype "passive"))
      (node (ref "SW61") (pin "2") (pinfunction "2_2") (pintype "passive"))
    )
    (net (code "118") (name "Net-(D62-K)") (class "Default")
      (node (ref "D62") (pin "2") (pinfunction "K_2") (pintype "passive"))
      (node (ref "SW62") (pin "2") (pinfunction "2_2") (pintype "passive"))
    )
    (net (code "119") (name "Net-(D63-K)") (class "Default")
      (node (ref "D63") (pin "2") (pinfunction "K_2") (pintype "passive"))
      (node (ref "SW63") (pin "2") (pinfunction "2_2") (pintype "passive"))
    )
    (net (code "120") (name "Net-(D64-K)") (class "Default")
      (node (ref "D64") (pin "2") (pinfunction "K_2") (pintype "passive"))
      (node (ref "SW64") (pin "2") (pinfunction "2_2") (pintype "passive"))
    )
    (net (code "121") (name "Net-(D65-K)") (class "Default")
      (node (ref "D65") (pin "2") (pinfunction "K_2") (pintype "passive"))
      (node (ref "SW65") (pin "2") (pinfunction "2_2") (pintype "passive"))
    )
    (net (code "122") (name "Net-(D66-K)") (class "Default")
      (node (ref "D66") (pin "2") (pinfunction "K_2") (pintype "passive"))
      (node (ref "SW66") (pin "2") (pinfunction "2_2") (pintype "passive"))
    )
    (net (code "123") (name "Net-(D67-K)") (class "Default")
      (node (ref "D67") (pin "2") (pinfunction "K_2") (pintype "passive"))
      (node (ref "SW67") (pin "2") (pinfunction "2_2") (pintype "passive"))
    )
    (net (code "124") (name "Net-(D68-K)") (class "Default")
      (node (ref "D68") (pin "2") (pinfunction "K_2") (pintype "passive"))
      (node (ref "SW68") (pin "2") (pinfunction "2_2") (pintype "passive"))
    )
    (net (code "125") (name "Net-(D69-K)") (class "Default")
      (node (ref "D69") (pin "2") (pinfunction "K_2") (pintype "passive"))
      (node (ref "SW69") (pin "2") (pinfunction "2_2") (pintype "passive"))
    )
    (net (code "126") (name "Net-(D70-K)") (class "Default")
      (node (ref "D70") (pin "2") (pinfunction "K_2") (pintype "passive"))
      (node (ref "SW70") (pin "2") (pinfunction "2_2") (pintype "passive"))
    )
    (net (code "127") (name "Net-(D71-K)") (class "Default")
      (node (ref "D71") (pin "2") (pinfunction "K_2") (pintype "passive"))
      (node (ref "SW71") (pin "2") (pinfunction "2_2") (pintype "passive"))
    )
    (net (code "128") (name "Net-(D72-K)") (class "Default")
      (node (ref "D72") (pin "2") (pinfunction "K_2") (pintype "passive"))
      (node (ref "SW72") (pin "2") (pinfunction "2_2") (pintype "passive"))
    )
    (net (code "129") (name "Net-(D73-K)") (class "Default")
      (node (ref "D73") (pin "2") (pinfunction "K_2") (pintype "passive"))
      (node (ref "SW73") (pin "2") (pinfunction "2_2") (pintype "passive"))
    )
    (net (code "130") (name "Net-(D74-K)") (class "Default")
      (node (ref "D74") (pin "2") (pinfunction "K_2") (pintype "passive"))
      (node (ref "SW74") (pin "2") (pinfunction "2_2") (pintype "passive"))
    )
    (net (code "131") (name "Net-(D75-K)") (class "Default")
      (node (ref "D75") (pin "2") (pinfunction "K_2") (pintype "passive"))
      (node (ref "SW75") (pin "2") (pinfunction "2_2") (pintype "passive"))
    )
    (net (code "132") (name "Net-(D76-K)") (class "Default")
      (node (ref "D76") (pin "2") (pinfunction "K_2") (pintype "passive"))
      (node (ref "SW76") (pin "2") (pinfunction "2_2") (pintype "passive"))
    )
    (net (code "133") (name "Net-(D77-K)") (class "Default")
      (node (ref "D77") (pin "2") (pinfunction "K_2") (pintype "passive"))
      (node (ref "SW77") (pin "2") (pinfunction "2_2") (pintype "passive"))
    )
    (net (code "134") (name "Net-(D78-K)") (class "Default")
      (node (ref "D78") (pin "2") (pinfunction "K_2") (pintype "passive"))
      (node (ref "SW78") (pin "2") (pinfunction "2_2") (pintype "passive"))
    )
    (net (code "135") (name "Net-(D79-K)") (class "Default")
      (node (ref "D79") (pin "2") (pinfunction "K_2") (pintype "passive"))
      (node (ref "SW79") (pin "2") (pinfunction "2_2") (pintype "passive"))
    )
    (net (code "136") (name "Net-(D80-K)") (class "Default")
      (node (ref "D80") (pin "2") (pinfunction "K_2") (pintype "passive"))
      (node (ref "SW80") (pin "2") (pinfunction "2_2") (pintype "passive"))
    )
    (net (code "137") (name "Net-(D81-K)") (class "Default")
      (node (ref "D81") (pin "2") (pinfunction "K_2") (pintype "passive"))
      (node (ref "SW81") (pin "2") (pinfunction "2_2") (pintype "passive"))
    )
    (net (code "138") (name "Net-(D82-K)") (class "Default")
      (node (ref "D82") (pin "2") (pinfunction "K_2") (pintype "passive"))
      (node (ref "SW82") (pin "2") (pinfunction "2_2") (pintype "passive"))
    )
    (net (code "139") (name "Net-(D83-K)") (class "Default")
      (node (ref "D83") (pin "2") (pinfunction "K_2") (pintype "passive"))
      (node (ref "SW83") (pin "2") (pinfunction "2_2") (pintype "passive"))
    )
    (net (code "140") (name "Net-(D84-K)") (class "Default")
      (node (ref "D84") (pin "2") (pinfunction "K_2") (pintype "passive"))
      (node (ref "SW84") (pin "2") (pinfunction "2_2") (pintype "passive"))
    )
    (net (code "141") (name "Net-(D85-K)") (class "Default")
      (node (ref "D85") (pin "2") (pinfunction "K_2") (pintype "passive"))
      (node (ref "SW85") (pin "2") (pinfunction "2_2") (pintype "passive"))
    )
    (net (code "142") (name "Net-(D86-K)") (class "Default")
      (node (ref "D86") (pin "2") (pinfunction "K_2") (pintype "passive"))
      (node (ref "SW86") (pin "2") (pinfunction "2_2") (pintype "passive"))
    )
    (net (code "143") (name "Net-(D87-K)") (class "Default")
      (node (ref "D87") (pin "2") (pinfunction "K_2") (pintype "passive"))
      (node (ref "SW87") (pin "2") (pinfunction "2_2") (pintype "passive"))
    )
    (net (code "144") (name "Net-(D88-PadA)") (class "Default")
      (node (ref "D88") (pin "A") (pinfunction "A_A") (pintype "passive"))
      (node (ref "R1") (pin "2") (pinfunction "2_2") (pintype "passive"))
    )
    (net (code "145") (name "Net-(D89-PadA)") (class "Default")
      (node (ref "D89") (pin "A") (pinfunction "A_A") (pintype "passive"))
      (node (ref "R2") (pin "2") (pinfunction "2_2") (pintype "passive"))
    )
    (net (code "146") (name "Net-(D90-PadA)") (class "Default")
      (node (ref "D90") (pin "A") (pinfunction "A_A") (pintype "passive"))
      (node (ref "R3") (pin "2") (pinfunction "2_2") (pintype "passive"))
    )
    (net (code "147") (name "Net-(J1-A5___CC1)") (class "Default")
      (node (ref "J1") (pin "4") (pinfunction "A5___CC1_4") (pintype "passive"))
      (node (ref "R7") (pin "2") (pinfunction "2_2") (pintype "passive"))
    )
    (net (code "148") (name "Net-(J1-B5___CC2)") (class "Default")
      (node (ref "J1") (pin "10") (pinfunction "B5___CC2_10") (pintype "passive"))
      (node (ref "R6") (pin "2") (pinfunction "2_2") (pintype "passive"))
    )
    (net (code "149") (name "unconnected-(J1-A8___SBU1-Pad9)") (class "Default")
      (node (ref "J1") (pin "9") (pinfunction "A8___SBU1_9") (pintype "passive"))
    )
    (net (code "150") (name "unconnected-(J1-B8___SBU2-Pad3)") (class "Default")
      (node (ref "J1") (pin "3") (pinfunction "B8___SBU2_3") (pintype "passive"))
    )
    (net (code "151") (name "unconnected-(JP1-Pad1)") (class "Default")
      (node (ref "JP1") (pin "1") (pinfunction "1_1") (pintype "passive"))
    )
    (net (code "152") (name "unconnected-(JP1-Pad2)") (class "Default")
      (node (ref "JP1") (pin "2") (pinfunction "2_2") (pintype "passive"))
    )
    (net (code "153") (name "unconnected-(JP1-Pad3)") (class "Default")
      (node (ref "JP1") (pin "3") (pinfunction "3_3") (pintype "passive"))
    )
    (net (code "154") (name "unconnected-(JP1-Pad4)") (class "Default")
      (node (ref "JP1") (pin "4") (pinfunction "4_4") (pintype "passive"))
    )
    (net (code "155") (name "unconnected-(JP2-Pad1)") (class "Default")
      (node (ref "JP2") (pin "1") (pinfunction "1_1") (pintype "passive"))
    )
    (net (code "156") (name "unconnected-(JP2-Pad2)") (class "Default")
      (node (ref "JP2") (pin "2") (pinfunction "2_2") (pintype "passive"))
    )
    (net (code "157") (name "unconnected-(JP2-Pad3)") (class "Default")
      (node (ref "JP2") (pin "3") (pinfunction "3_3") (pintype "passive"))
    )
    (net (code "158") (name "unconnected-(JP2-Pad4)") (class "Default")
      (node (ref "JP2") (pin "4") (pinfunction "4_4") (pintype "passive"))
    )
    (net (code "159") (name "unconnected-(JP3-Pad1)") (class "Default")
      (node (ref "JP3") (pin "1") (pinfunction "1_1") (pintype "passive"))
    )
    (net (code "160") (name "unconnected-(JP3-Pad2)") (class "Default")
      (node (ref "JP3") (pin "2") (pinfunction "2_2") (pintype "passive"))
    )
    (net (code "161") (name "unconnected-(JP3-Pad3)") (class "Default")
      (node (ref "JP3") (pin "3") (pinfunction "3_3") (pintype "passive"))
    )
    (net (code "162") (name "unconnected-(JP3-Pad4)") (class "Default")
      (node (ref "JP3") (pin "4") (pinfunction "4_4") (pintype "passive"))
    )
    (net (code "163") (name "unconnected-(JP4-Pad1)") (class "Default")
      (node (ref "JP4") (pin "1") (pinfunction "1_1") (pintype "passive"))
    )
    (net (code "164") (name "unconnected-(JP4-Pad2)") (class "Default")
      (node (ref "JP4") (pin "2") (pinfunction "2_2") (pintype "passive"))
    )
    (net (code "165") (name "unconnected-(JP4-Pad3)") (class "Default")
      (node (ref "JP4") (pin "3") (pinfunction "3_3") (pintype "passive"))
    )
    (net (code "166") (name "unconnected-(JP4-Pad4)") (class "Default")
      (node (ref "JP4") (pin "4") (pinfunction "4_4") (pintype "passive"))
    )
    (net (code "167") (name "unconnected-(JP5-Pad1)") (class "Default")
      (node (ref "JP5") (pin "1") (pinfunction "1_1") (pintype "passive"))
    )
    (net (code "168") (name "unconnected-(JP5-Pad2)") (class "Default")
      (node (ref "JP5") (pin "2") (pinfunction "2_2") (pintype "passive"))
    )
    (net (code "169") (name "unconnected-(JP5-Pad3)") (class "Default")
      (node (ref "JP5") (pin "3") (pinfunction "3_3") (pintype "passive"))
    )
    (net (code "170") (name "unconnected-(JP5-Pad4)") (class "Default")
      (node (ref "JP5") (pin "4") (pinfunction "4_4") (pintype "passive"))
    )
  )
)
